# ARK.net
KiCad netlist of a schematic drawn in EAGLE
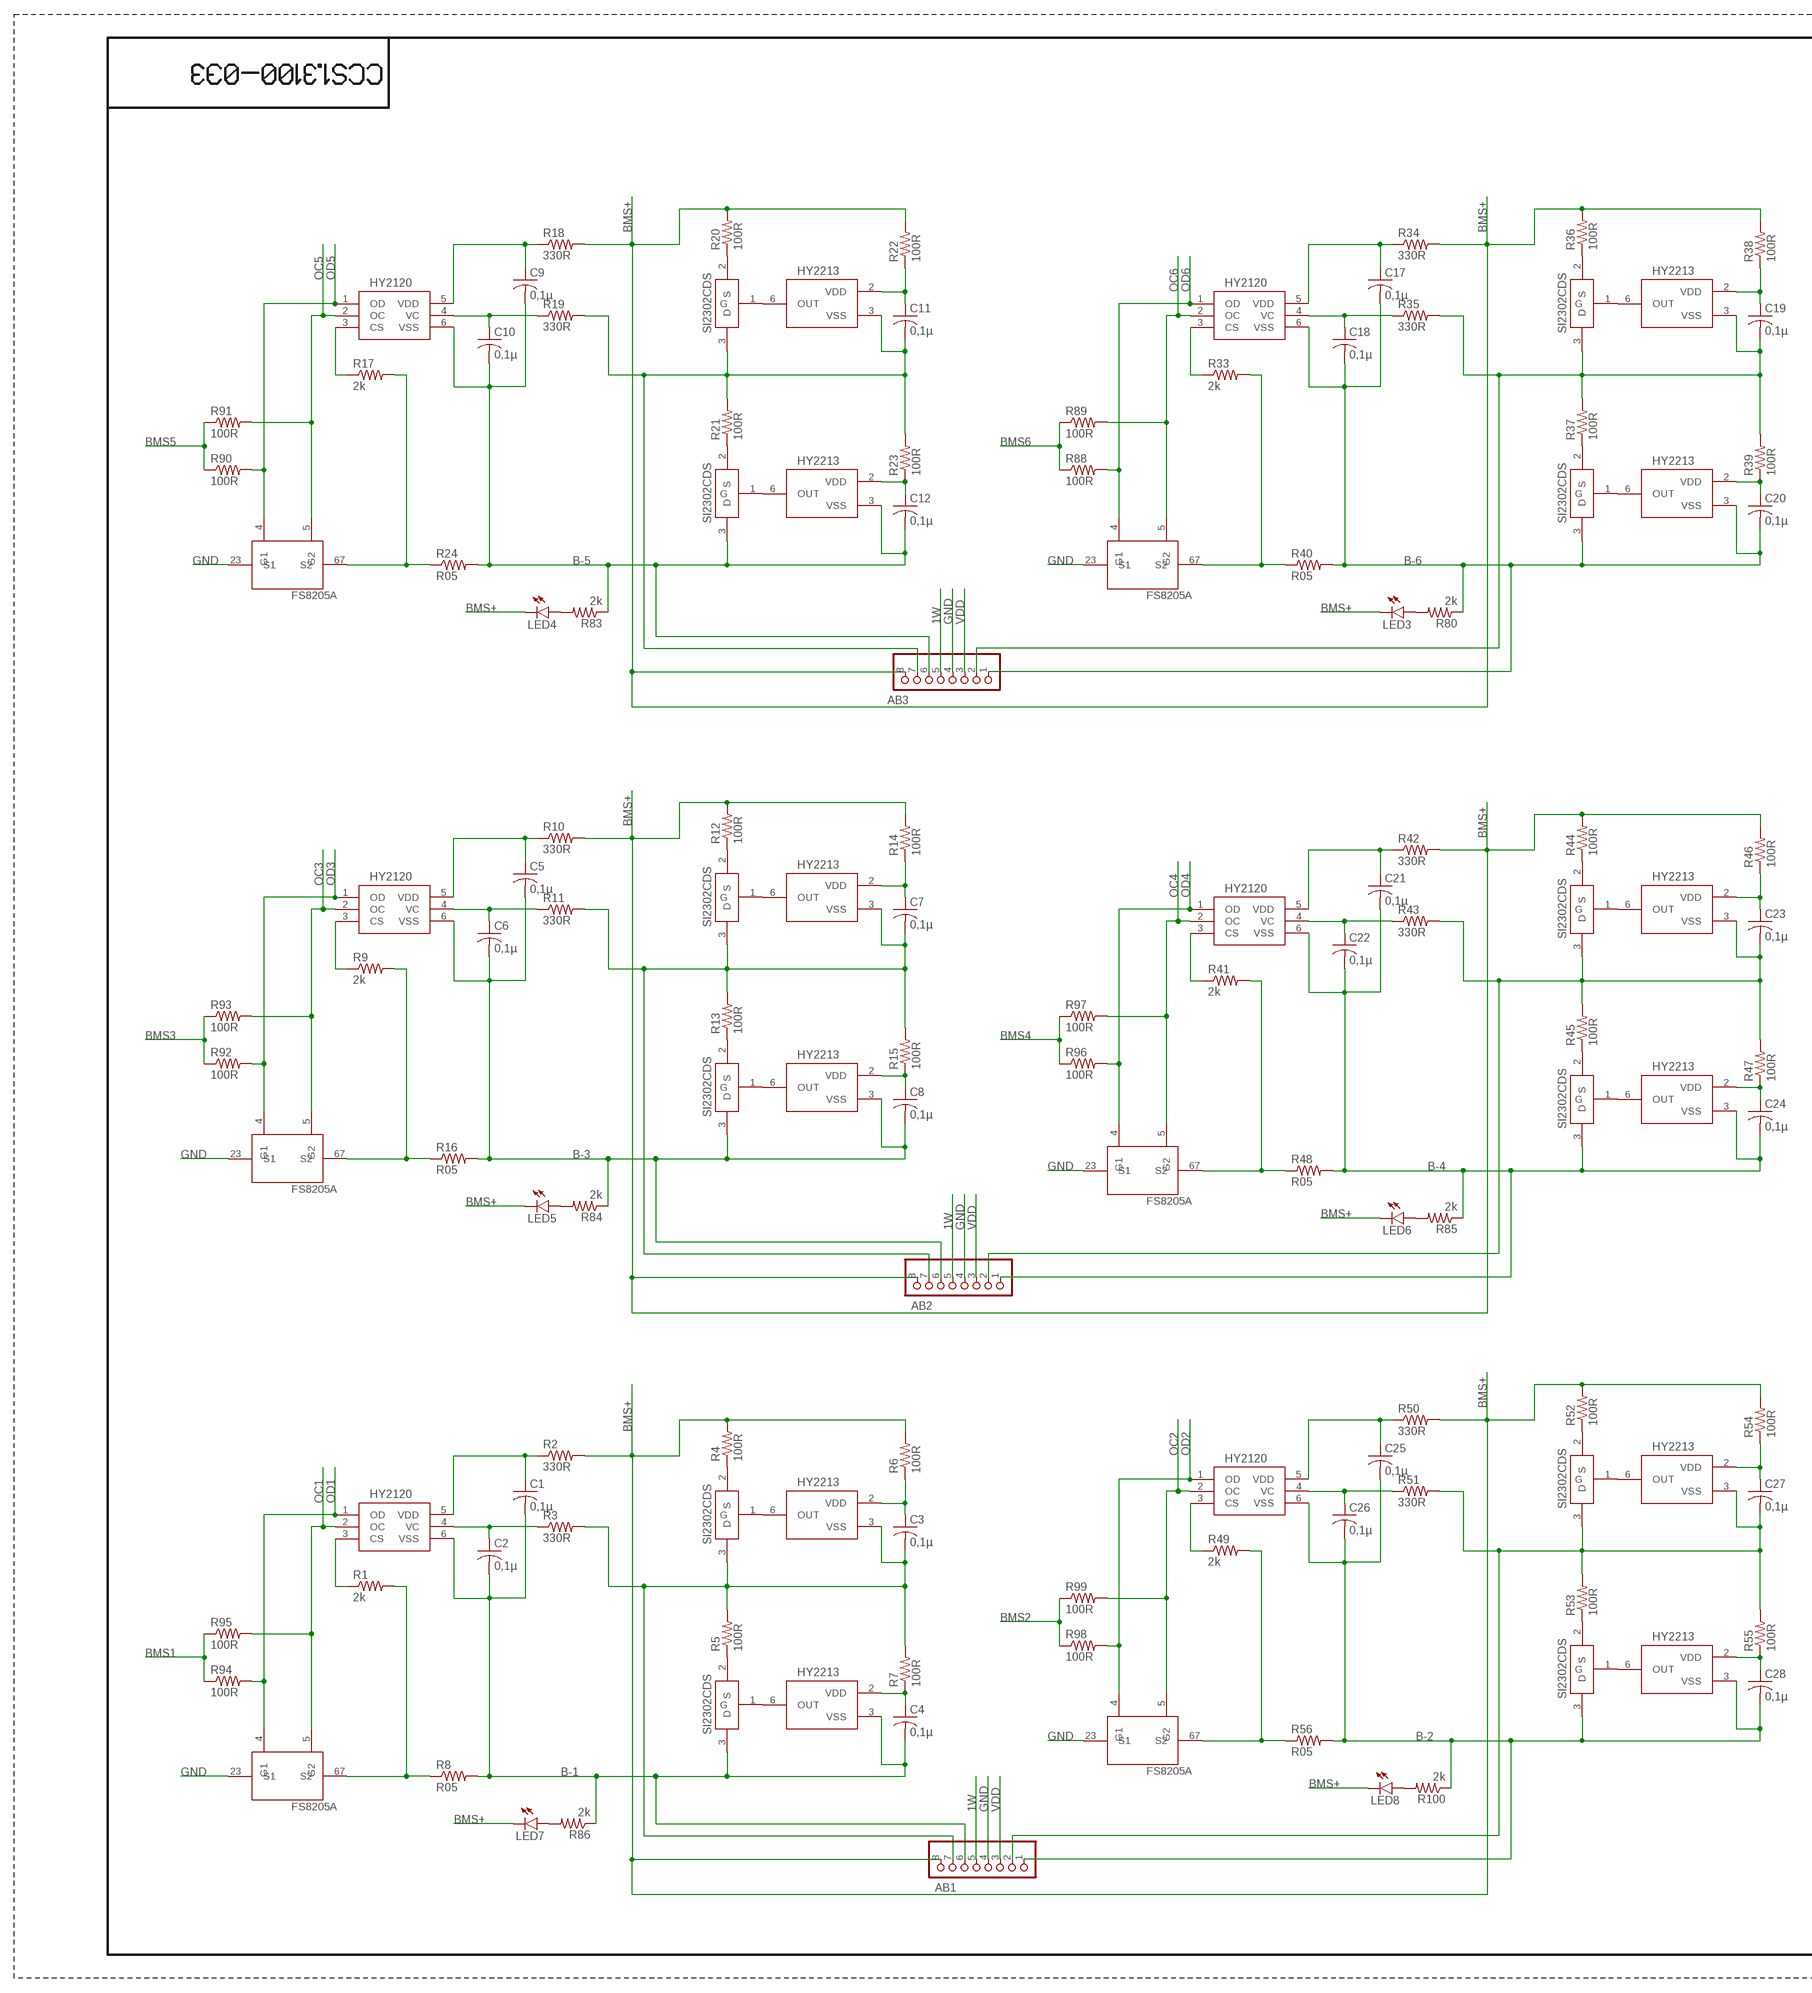
[diagram p0: schematic, sheet 1, part 1 of 2]
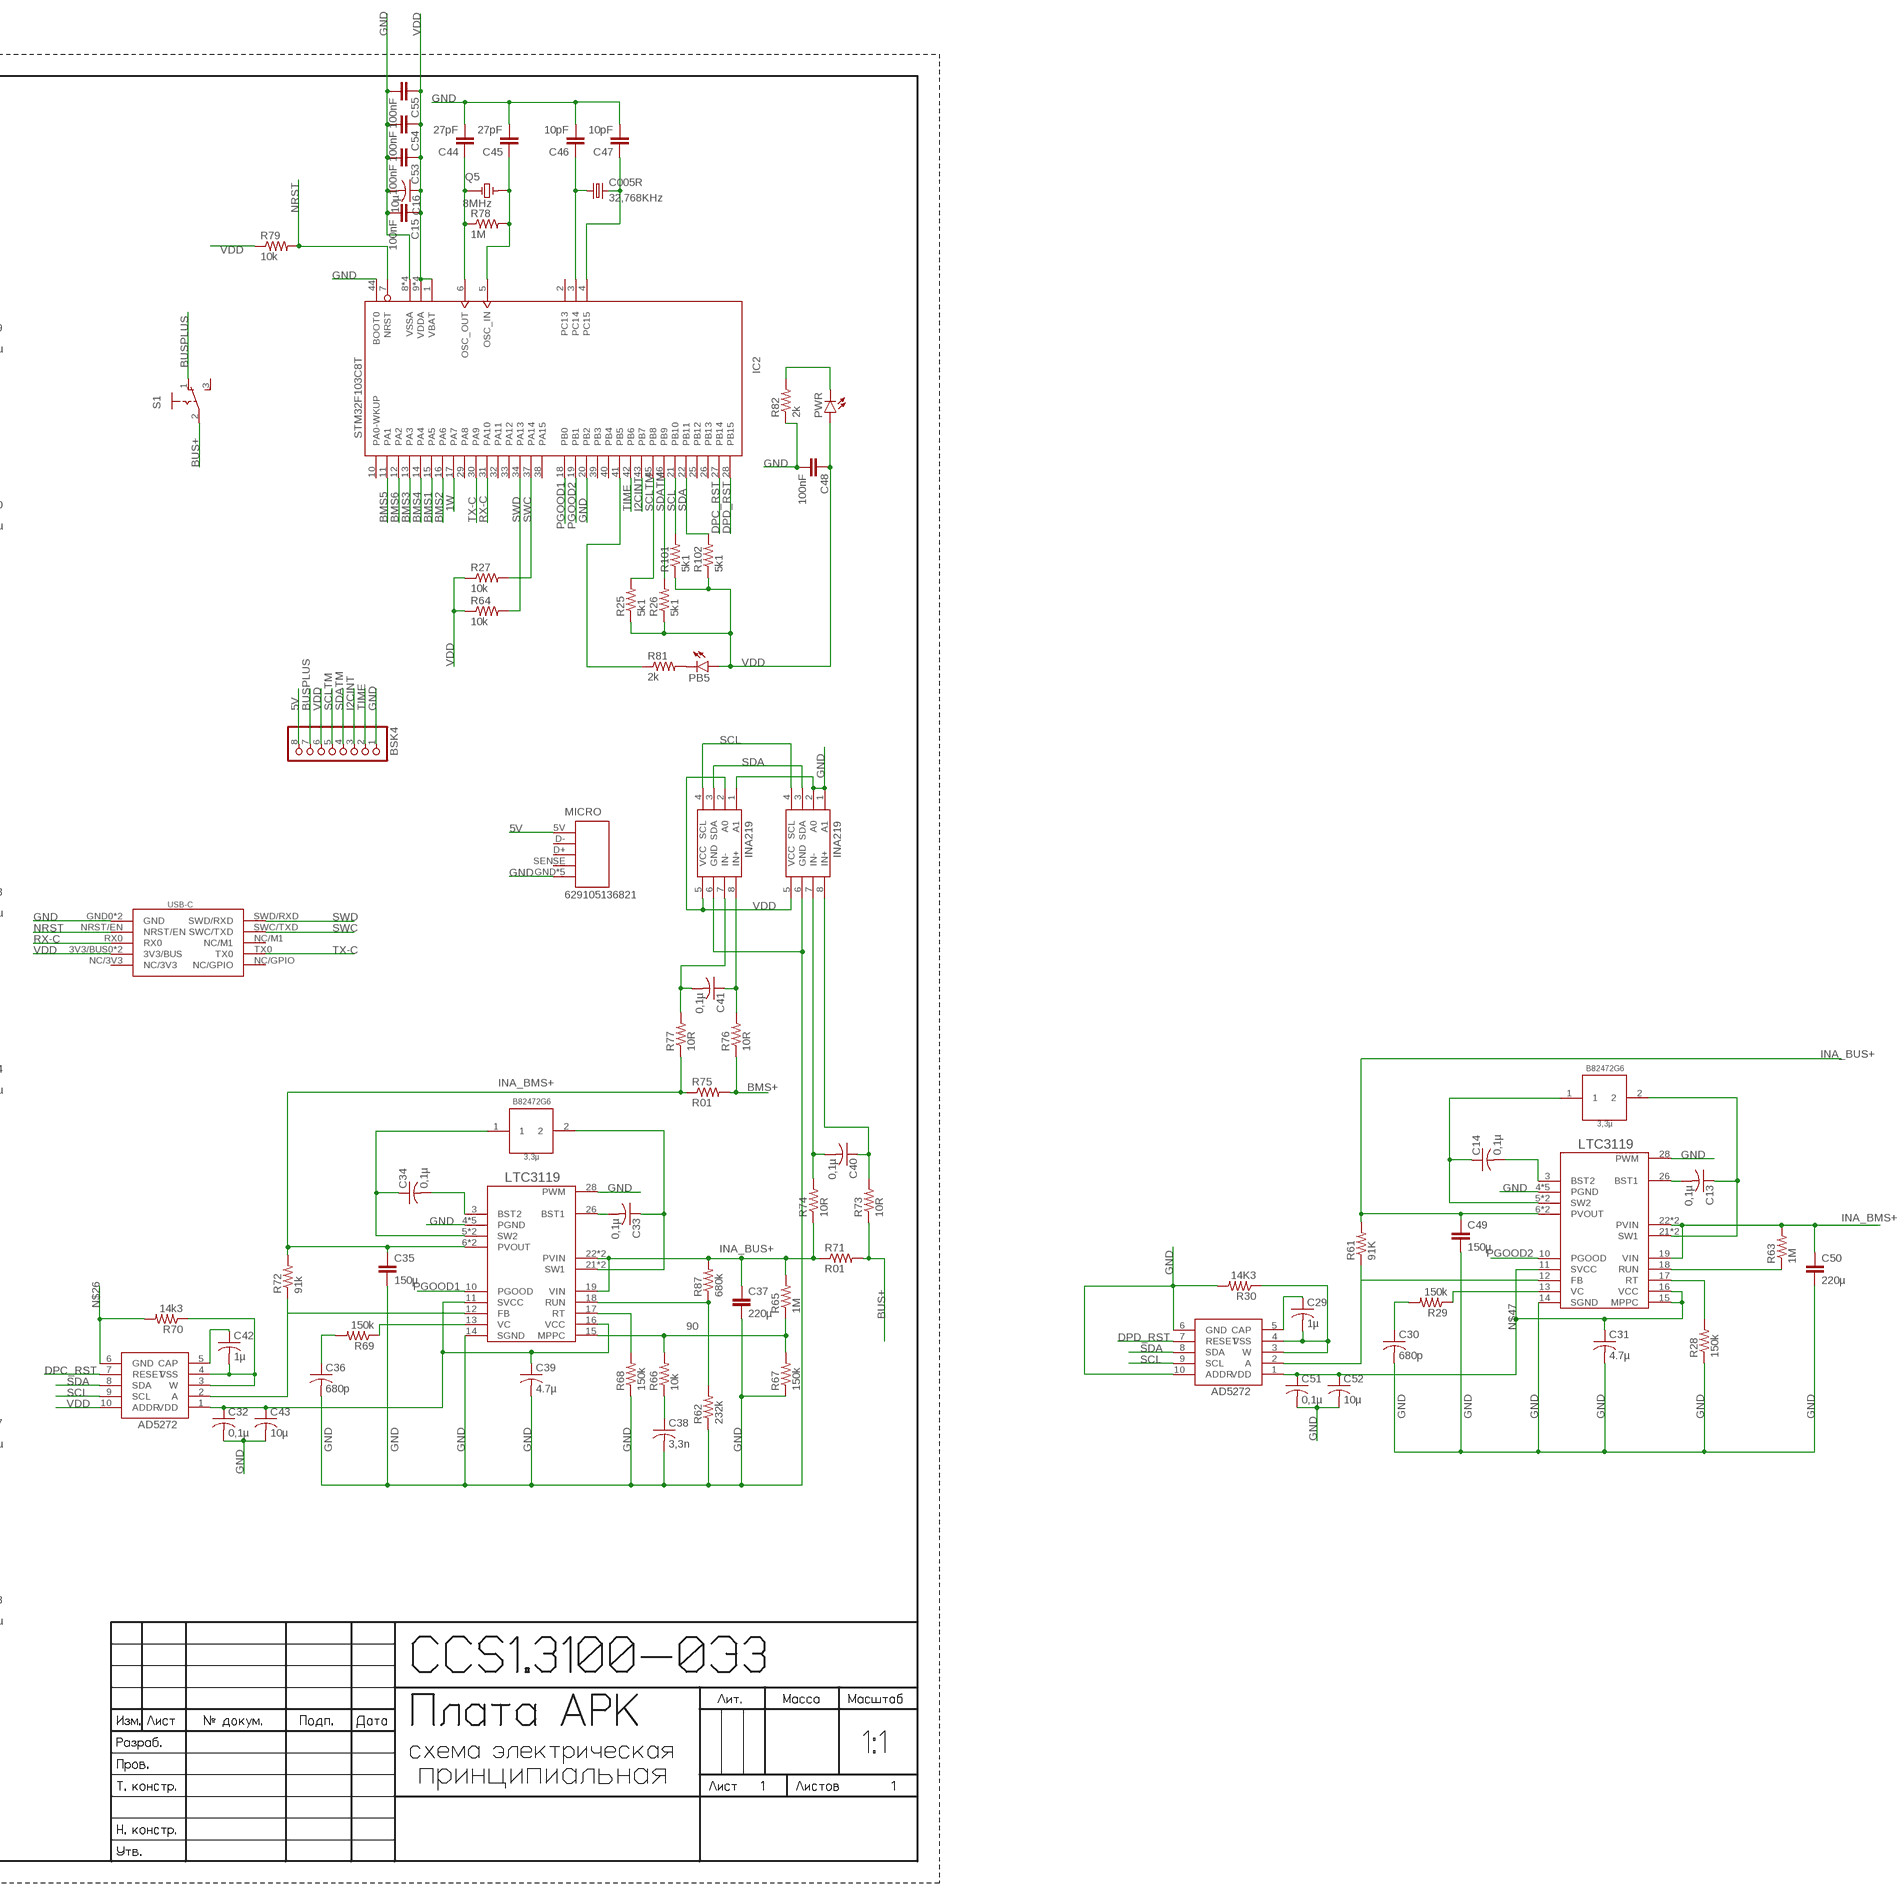
[diagram p1: schematic, sheet 1, part 2 of 2]

(export (version "E")
  (design (tool "Eeschema 10.0.6"))
  (components
    (comp (ref "3,3µH")
      (value "3,3µ")
      (footprint "eagle-import:B82472G6")
      (libsource (lib "eagle-import") (part "B82472G6"))
    )
    (comp (ref "3,3µH1")
      (value "3,3µ")
      (footprint "eagle-import:B82472G6")
      (libsource (lib "eagle-import") (part "B82472G6"))
    )
    (comp (ref "AB1")
      (value "PINHD-1X8")
      (footprint "eagle-import:1X08")
      (libsource (lib "eagle-import") (part "PINHD-1X8"))
    )
    (comp (ref "AB2")
      (value "PINHD-1X8")
      (footprint "eagle-import:1X08")
      (libsource (lib "eagle-import") (part "PINHD-1X8"))
    )
    (comp (ref "AB3")
      (value "PINHD-1X8")
      (footprint "eagle-import:1X08")
      (libsource (lib "eagle-import") (part "PINHD-1X8"))
    )
    (comp (ref "AD5272#2")
      (value "AD5272")
      (footprint "eagle-import:AD5272")
      (libsource (lib "eagle-import") (part "AD5272"))
    )
    (comp (ref "BSK4")
      (value "PINHD-1X8")
      (footprint "eagle-import:1X08")
      (libsource (lib "eagle-import") (part "PINHD-1X8"))
    )
    (comp (ref "C1")
      (value "0,1µ")
      (footprint "eagle-import:C0603")
      (libsource (lib "eagle-import") (part "C-USC0603"))
    )
    (comp (ref "C2")
      (value "0,1µ")
      (footprint "eagle-import:C0603")
      (libsource (lib "eagle-import") (part "C-USC0603"))
    )
    (comp (ref "C3")
      (value "0,1µ")
      (footprint "eagle-import:C0603")
      (libsource (lib "eagle-import") (part "C-USC0603"))
    )
    (comp (ref "C4")
      (value "0,1µ")
      (footprint "eagle-import:C0603")
      (libsource (lib "eagle-import") (part "C-USC0603"))
    )
    (comp (ref "C5")
      (value "0,1µ")
      (footprint "eagle-import:C0603")
      (libsource (lib "eagle-import") (part "C-USC0603"))
    )
    (comp (ref "C005R")
      (value "32,768KHz")
      (footprint "eagle-import:C005R")
      (libsource (lib "eagle-import") (part "C005R"))
    )
    (comp (ref "C6")
      (value "0,1µ")
      (footprint "eagle-import:C0603")
      (libsource (lib "eagle-import") (part "C-USC0603"))
    )
    (comp (ref "C7")
      (value "0,1µ")
      (footprint "eagle-import:C0603")
      (libsource (lib "eagle-import") (part "C-USC0603"))
    )
    (comp (ref "C8")
      (value "0,1µ")
      (footprint "eagle-import:C0603")
      (libsource (lib "eagle-import") (part "C-USC0603"))
    )
    (comp (ref "C9")
      (value "0,1µ")
      (footprint "eagle-import:C0603")
      (libsource (lib "eagle-import") (part "C-USC0603"))
    )
    (comp (ref "C10")
      (value "0,1µ")
      (footprint "eagle-import:C0603")
      (libsource (lib "eagle-import") (part "C-USC0603"))
    )
    (comp (ref "C11")
      (value "0,1µ")
      (footprint "eagle-import:C0603")
      (libsource (lib "eagle-import") (part "C-USC0603"))
    )
    (comp (ref "C12")
      (value "0,1µ")
      (footprint "eagle-import:C0603")
      (libsource (lib "eagle-import") (part "C-USC0603"))
    )
    (comp (ref "C13")
      (value "0,1µ")
      (footprint "eagle-import:C0603")
      (libsource (lib "eagle-import") (part "C-USC0603"))
    )
    (comp (ref "C14")
      (value "0,1µ")
      (footprint "eagle-import:C0603")
      (libsource (lib "eagle-import") (part "C-USC0603"))
    )
    (comp (ref "C15")
      (value "100nF")
      (footprint "eagle-import:C0603")
      (libsource (lib "eagle-import") (part "C-EUC0603"))
    )
    (comp (ref "C16")
      (value "10µ")
      (footprint "eagle-import:C1206")
      (libsource (lib "eagle-import") (part "C-USC1206"))
    )
    (comp (ref "C17")
      (value "0,1µ")
      (footprint "eagle-import:C0603")
      (libsource (lib "eagle-import") (part "C-USC0603"))
    )
    (comp (ref "C18")
      (value "0,1µ")
      (footprint "eagle-import:C0603")
      (libsource (lib "eagle-import") (part "C-USC0603"))
    )
    (comp (ref "C19")
      (value "0,1µ")
      (footprint "eagle-import:C0603")
      (libsource (lib "eagle-import") (part "C-USC0603"))
    )
    (comp (ref "C20")
      (value "0,1µ")
      (footprint "eagle-import:C0603")
      (libsource (lib "eagle-import") (part "C-USC0603"))
    )
    (comp (ref "C21")
      (value "0,1µ")
      (footprint "eagle-import:C0603")
      (libsource (lib "eagle-import") (part "C-USC0603"))
    )
    (comp (ref "C22")
      (value "0,1µ")
      (footprint "eagle-import:C0603")
      (libsource (lib "eagle-import") (part "C-USC0603"))
    )
    (comp (ref "C23")
      (value "0,1µ")
      (footprint "eagle-import:C0603")
      (libsource (lib "eagle-import") (part "C-USC0603"))
    )
    (comp (ref "C24")
      (value "0,1µ")
      (footprint "eagle-import:C0603")
      (libsource (lib "eagle-import") (part "C-USC0603"))
    )
    (comp (ref "C25")
      (value "0,1µ")
      (footprint "eagle-import:C0603")
      (libsource (lib "eagle-import") (part "C-USC0603"))
    )
    (comp (ref "C26")
      (value "0,1µ")
      (footprint "eagle-import:C0603")
      (libsource (lib "eagle-import") (part "C-USC0603"))
    )
    (comp (ref "C27")
      (value "0,1µ")
      (footprint "eagle-import:C0603")
      (libsource (lib "eagle-import") (part "C-USC0603"))
    )
    (comp (ref "C28")
      (value "0,1µ")
      (footprint "eagle-import:C0603")
      (libsource (lib "eagle-import") (part "C-USC0603"))
    )
    (comp (ref "C29")
      (value "1µ")
      (footprint "eagle-import:C0603")
      (libsource (lib "eagle-import") (part "C-USC0603"))
    )
    (comp (ref "C30")
      (value "680p")
      (footprint "eagle-import:C0603")
      (libsource (lib "eagle-import") (part "C-USC0603"))
    )
    (comp (ref "C31")
      (value "4.7µ")
      (footprint "eagle-import:C1206")
      (libsource (lib "eagle-import") (part "C-USC1206"))
    )
    (comp (ref "C32")
      (value "0,1µ")
      (footprint "eagle-import:C0603")
      (libsource (lib "eagle-import") (part "C-USC0603"))
    )
    (comp (ref "C33")
      (value "0,1µ")
      (footprint "eagle-import:C0603")
      (libsource (lib "eagle-import") (part "C-USC0603"))
    )
    (comp (ref "C34")
      (value "0,1µ")
      (footprint "eagle-import:C0603")
      (libsource (lib "eagle-import") (part "C-USC0603"))
    )
    (comp (ref "C35")
      (value "150µ")
      (footprint "eagle-import:ECAP150")
      (libsource (lib "eagle-import") (part "ECAPECAP150"))
    )
    (comp (ref "C36")
      (value "680p")
      (footprint "eagle-import:C0603")
      (libsource (lib "eagle-import") (part "C-USC0603"))
    )
    (comp (ref "C37")
      (value "220µ")
      (footprint "eagle-import:ECAP220")
      (libsource (lib "eagle-import") (part "ECAPECAP220"))
    )
    (comp (ref "C38")
      (value "3,3n")
      (footprint "eagle-import:C0603")
      (libsource (lib "eagle-import") (part "C-USC0603"))
    )
    (comp (ref "C39")
      (value "4.7µ")
      (footprint "eagle-import:C1206")
      (libsource (lib "eagle-import") (part "C-USC1206"))
    )
    (comp (ref "C40")
      (value "0,1µ")
      (footprint "eagle-import:C0603")
      (libsource (lib "eagle-import") (part "C-USC0603"))
    )
    (comp (ref "C41")
      (value "0,1µ")
      (footprint "eagle-import:C0603")
      (libsource (lib "eagle-import") (part "C-USC0603"))
    )
    (comp (ref "C42")
      (value "1µ")
      (footprint "eagle-import:C0603")
      (libsource (lib "eagle-import") (part "C-USC0603"))
    )
    (comp (ref "C43")
      (value "10µ")
      (footprint "eagle-import:C1206")
      (libsource (lib "eagle-import") (part "C-USC1206"))
    )
    (comp (ref "C44")
      (value "27pF")
      (footprint "eagle-import:C0603")
      (libsource (lib "eagle-import") (part "C-EUC0603"))
    )
    (comp (ref "C45")
      (value "27pF")
      (footprint "eagle-import:C0603")
      (libsource (lib "eagle-import") (part "C-EUC0603"))
    )
    (comp (ref "C46")
      (value "10pF")
      (footprint "eagle-import:C0603")
      (libsource (lib "eagle-import") (part "C-EUC0603"))
    )
    (comp (ref "C47")
      (value "10pF")
      (footprint "eagle-import:C0603")
      (libsource (lib "eagle-import") (part "C-EUC0603"))
    )
    (comp (ref "C48")
      (value "100nF")
      (footprint "eagle-import:C0603")
      (libsource (lib "eagle-import") (part "C-EUC0603"))
    )
    (comp (ref "C49")
      (value "150µ")
      (footprint "eagle-import:ECAP150")
      (libsource (lib "eagle-import") (part "ECAPECAP150"))
    )
    (comp (ref "C50")
      (value "220µ")
      (footprint "eagle-import:ECAP220")
      (libsource (lib "eagle-import") (part "ECAPECAP220"))
    )
    (comp (ref "C51")
      (value "0,1µ")
      (footprint "eagle-import:C0603")
      (libsource (lib "eagle-import") (part "C-USC0603"))
    )
    (comp (ref "C52")
      (value "10µ")
      (footprint "eagle-import:C1206")
      (libsource (lib "eagle-import") (part "C-USC1206"))
    )
    (comp (ref "C53")
      (value "100nF")
      (footprint "eagle-import:C0603")
      (libsource (lib "eagle-import") (part "C-EUC0603"))
    )
    (comp (ref "C54")
      (value "100nF")
      (footprint "eagle-import:C0603")
      (libsource (lib "eagle-import") (part "C-EUC0603"))
    )
    (comp (ref "C55")
      (value "100nF")
      (footprint "eagle-import:C0603")
      (libsource (lib "eagle-import") (part "C-EUC0603"))
    )
    (comp (ref "IC2")
      (value "STM32F103C8T")
      (footprint "eagle-import:LQFP48")
      (libsource (lib "eagle-import") (part "STM32F103CT8"))
    )
    (comp (ref "INA219#1")
      (value "INA219AID")
      (footprint "eagle-import:INA219AID")
      (libsource (lib "eagle-import") (part "INA219AID"))
    )
    (comp (ref "LED3")
      (value "LEDCHIPLED_0603")
      (footprint "eagle-import:CHIPLED_0603")
      (libsource (lib "eagle-import") (part "LEDCHIPLED_0603"))
    )
    (comp (ref "LED4")
      (value "LEDCHIPLED_0603")
      (footprint "eagle-import:CHIPLED_0603")
      (libsource (lib "eagle-import") (part "LEDCHIPLED_0603"))
    )
    (comp (ref "LED5")
      (value "LEDCHIPLED_0603")
      (footprint "eagle-import:CHIPLED_0603")
      (libsource (lib "eagle-import") (part "LEDCHIPLED_0603"))
    )
    (comp (ref "LED6")
      (value "LEDCHIPLED_0603")
      (footprint "eagle-import:CHIPLED_0603")
      (libsource (lib "eagle-import") (part "LEDCHIPLED_0603"))
    )
    (comp (ref "LED7")
      (value "LEDCHIPLED_0603")
      (footprint "eagle-import:CHIPLED_0603")
      (libsource (lib "eagle-import") (part "LEDCHIPLED_0603"))
    )
    (comp (ref "LED8")
      (value "LEDCHIPLED_0603")
      (footprint "eagle-import:CHIPLED_0603")
      (libsource (lib "eagle-import") (part "LEDCHIPLED_0603"))
    )
    (comp (ref "MICRO")
      (value "629105136821")
      (footprint "eagle-import:629105136821")
      (libsource (lib "eagle-import") (part "629105136821"))
    )
    (comp (ref "PB5")
      (value "LEDCHIPLED_0603")
      (footprint "eagle-import:CHIPLED_0603")
      (libsource (lib "eagle-import") (part "LEDCHIPLED_0603"))
    )
    (comp (ref "PWR")
      (value "LEDCHIPLED_0603")
      (footprint "eagle-import:CHIPLED_0603")
      (libsource (lib "eagle-import") (part "LEDCHIPLED_0603"))
    )
    (comp (ref "Q5")
      (value "8MHz")
      (footprint "eagle-import:XTAL_9C-8.000MEEJ-T")
      (fields (field (name "MF") "TXC CORPORATION") (field (name "MP") "9C-8.000MEEJ-T"))
      (libsource (lib "eagle-import") (part "9C-8.000MEEJ-T"))
    )
    (comp (ref "R1")
      (value "2k")
      (footprint "eagle-import:R0603")
      (libsource (lib "eagle-import") (part "resistor_348_R-US_R0603"))
    )
    (comp (ref "R2")
      (value "330R")
      (footprint "eagle-import:R0603")
      (libsource (lib "eagle-import") (part "resistor_348_R-US_R0603"))
    )
    (comp (ref "R3")
      (value "330R")
      (footprint "eagle-import:R0603")
      (libsource (lib "eagle-import") (part "resistor_348_R-US_R0603"))
    )
    (comp (ref "R4")
      (value "100R")
      (footprint "eagle-import:R0603")
      (libsource (lib "eagle-import") (part "resistor_348_R-US_R0603"))
    )
    (comp (ref "R5")
      (value "100R")
      (footprint "eagle-import:R0603")
      (libsource (lib "eagle-import") (part "resistor_348_R-US_R0603"))
    )
    (comp (ref "R6")
      (value "100R")
      (footprint "eagle-import:R0603")
      (libsource (lib "eagle-import") (part "resistor_348_R-US_R0603"))
    )
    (comp (ref "R7")
      (value "100R")
      (footprint "eagle-import:R0603")
      (libsource (lib "eagle-import") (part "resistor_348_R-US_R0603"))
    )
    (comp (ref "R8")
      (value "R05")
      (footprint "eagle-import:R2512")
      (libsource (lib "eagle-import") (part "R-US_R2512"))
    )
    (comp (ref "R9")
      (value "2k")
      (footprint "eagle-import:R0603")
      (libsource (lib "eagle-import") (part "resistor_348_R-US_R0603"))
    )
    (comp (ref "R10")
      (value "330R")
      (footprint "eagle-import:R0603")
      (libsource (lib "eagle-import") (part "resistor_348_R-US_R0603"))
    )
    (comp (ref "R11")
      (value "330R")
      (footprint "eagle-import:R0603")
      (libsource (lib "eagle-import") (part "resistor_348_R-US_R0603"))
    )
    (comp (ref "R12")
      (value "100R")
      (footprint "eagle-import:R0603")
      (libsource (lib "eagle-import") (part "resistor_348_R-US_R0603"))
    )
    (comp (ref "R13")
      (value "100R")
      (footprint "eagle-import:R0603")
      (libsource (lib "eagle-import") (part "resistor_348_R-US_R0603"))
    )
    (comp (ref "R14")
      (value "100R")
      (footprint "eagle-import:R0603")
      (libsource (lib "eagle-import") (part "resistor_348_R-US_R0603"))
    )
    (comp (ref "R15")
      (value "100R")
      (footprint "eagle-import:R0603")
      (libsource (lib "eagle-import") (part "resistor_348_R-US_R0603"))
    )
    (comp (ref "R16")
      (value "R05")
      (footprint "eagle-import:R2512")
      (libsource (lib "eagle-import") (part "R-US_R2512"))
    )
    (comp (ref "R17")
      (value "2k")
      (footprint "eagle-import:R0603")
      (libsource (lib "eagle-import") (part "resistor_348_R-US_R0603"))
    )
    (comp (ref "R18")
      (value "330R")
      (footprint "eagle-import:R0603")
      (libsource (lib "eagle-import") (part "resistor_348_R-US_R0603"))
    )
    (comp (ref "R19")
      (value "330R")
      (footprint "eagle-import:R0603")
      (libsource (lib "eagle-import") (part "resistor_348_R-US_R0603"))
    )
    (comp (ref "R20")
      (value "100R")
      (footprint "eagle-import:R0603")
      (libsource (lib "eagle-import") (part "resistor_348_R-US_R0603"))
    )
    (comp (ref "R21")
      (value "100R")
      (footprint "eagle-import:R0603")
      (libsource (lib "eagle-import") (part "resistor_348_R-US_R0603"))
    )
    (comp (ref "R22")
      (value "100R")
      (footprint "eagle-import:R0603")
      (libsource (lib "eagle-import") (part "resistor_348_R-US_R0603"))
    )
    (comp (ref "R23")
      (value "100R")
      (footprint "eagle-import:R0603")
      (libsource (lib "eagle-import") (part "resistor_348_R-US_R0603"))
    )
    (comp (ref "R24")
      (value "R05")
      (footprint "eagle-import:R2512")
      (libsource (lib "eagle-import") (part "R-US_R2512"))
    )
    (comp (ref "R25")
      (value "5k1")
      (footprint "eagle-import:R0603")
      (libsource (lib "eagle-import") (part "resistor_348_R-US_R0603"))
    )
    (comp (ref "R26")
      (value "5k1")
      (footprint "eagle-import:R0603")
      (libsource (lib "eagle-import") (part "resistor_348_R-US_R0603"))
    )
    (comp (ref "R27")
      (value "10k")
      (footprint "eagle-import:R0603")
      (libsource (lib "eagle-import") (part "resistor_348_R-US_R0603"))
    )
    (comp (ref "R28")
      (value "150k")
      (footprint "eagle-import:R0603")
      (libsource (lib "eagle-import") (part "resistor_348_R-US_R0603"))
    )
    (comp (ref "R29")
      (value "150k")
      (footprint "eagle-import:R0603")
      (libsource (lib "eagle-import") (part "resistor_348_R-US_R0603"))
    )
    (comp (ref "R30")
      (value "14K3")
      (footprint "eagle-import:R0603")
      (libsource (lib "eagle-import") (part "resistor_348_R-US_R0603"))
    )
    (comp (ref "R33")
      (value "2k")
      (footprint "eagle-import:R0603")
      (libsource (lib "eagle-import") (part "resistor_348_R-US_R0603"))
    )
    (comp (ref "R34")
      (value "330R")
      (footprint "eagle-import:R0603")
      (libsource (lib "eagle-import") (part "resistor_348_R-US_R0603"))
    )
    (comp (ref "R35")
      (value "330R")
      (footprint "eagle-import:R0603")
      (libsource (lib "eagle-import") (part "resistor_348_R-US_R0603"))
    )
    (comp (ref "R36")
      (value "100R")
      (footprint "eagle-import:R0603")
      (libsource (lib "eagle-import") (part "resistor_348_R-US_R0603"))
    )
    (comp (ref "R37")
      (value "100R")
      (footprint "eagle-import:R0603")
      (libsource (lib "eagle-import") (part "resistor_348_R-US_R0603"))
    )
    (comp (ref "R38")
      (value "100R")
      (footprint "eagle-import:R0603")
      (libsource (lib "eagle-import") (part "resistor_348_R-US_R0603"))
    )
    (comp (ref "R39")
      (value "100R")
      (footprint "eagle-import:R0603")
      (libsource (lib "eagle-import") (part "resistor_348_R-US_R0603"))
    )
    (comp (ref "R40")
      (value "R05")
      (footprint "eagle-import:R2512")
      (libsource (lib "eagle-import") (part "R-US_R2512"))
    )
    (comp (ref "R41")
      (value "2k")
      (footprint "eagle-import:R0603")
      (libsource (lib "eagle-import") (part "resistor_348_R-US_R0603"))
    )
    (comp (ref "R42")
      (value "330R")
      (footprint "eagle-import:R0603")
      (libsource (lib "eagle-import") (part "resistor_348_R-US_R0603"))
    )
    (comp (ref "R43")
      (value "330R")
      (footprint "eagle-import:R0603")
      (libsource (lib "eagle-import") (part "resistor_348_R-US_R0603"))
    )
    (comp (ref "R44")
      (value "100R")
      (footprint "eagle-import:R0603")
      (libsource (lib "eagle-import") (part "resistor_348_R-US_R0603"))
    )
    (comp (ref "R45")
      (value "100R")
      (footprint "eagle-import:R0603")
      (libsource (lib "eagle-import") (part "resistor_348_R-US_R0603"))
    )
    (comp (ref "R46")
      (value "100R")
      (footprint "eagle-import:R0603")
      (libsource (lib "eagle-import") (part "resistor_348_R-US_R0603"))
    )
    (comp (ref "R47")
      (value "100R")
      (footprint "eagle-import:R0603")
      (libsource (lib "eagle-import") (part "resistor_348_R-US_R0603"))
    )
    (comp (ref "R48")
      (value "R05")
      (footprint "eagle-import:R2512")
      (libsource (lib "eagle-import") (part "R-US_R2512"))
    )
    (comp (ref "R49")
      (value "2k")
      (footprint "eagle-import:R0603")
      (libsource (lib "eagle-import") (part "resistor_348_R-US_R0603"))
    )
    (comp (ref "R50")
      (value "330R")
      (footprint "eagle-import:R0603")
      (libsource (lib "eagle-import") (part "resistor_348_R-US_R0603"))
    )
    (comp (ref "R51")
      (value "330R")
      (footprint "eagle-import:R0603")
      (libsource (lib "eagle-import") (part "resistor_348_R-US_R0603"))
    )
    (comp (ref "R52")
      (value "100R")
      (footprint "eagle-import:R0603")
      (libsource (lib "eagle-import") (part "resistor_348_R-US_R0603"))
    )
    (comp (ref "R53")
      (value "100R")
      (footprint "eagle-import:R0603")
      (libsource (lib "eagle-import") (part "resistor_348_R-US_R0603"))
    )
    (comp (ref "R54")
      (value "100R")
      (footprint "eagle-import:R0603")
      (libsource (lib "eagle-import") (part "resistor_348_R-US_R0603"))
    )
    (comp (ref "R55")
      (value "100R")
      (footprint "eagle-import:R0603")
      (libsource (lib "eagle-import") (part "resistor_348_R-US_R0603"))
    )
    (comp (ref "R56")
      (value "R05")
      (footprint "eagle-import:R2512")
      (libsource (lib "eagle-import") (part "R-US_R2512"))
    )
    (comp (ref "R61")
      (value "91K")
      (footprint "eagle-import:R0603")
      (libsource (lib "eagle-import") (part "resistor_348_R-US_R0603"))
    )
    (comp (ref "R62")
      (value "232k")
      (footprint "eagle-import:R0603")
      (libsource (lib "eagle-import") (part "resistor_348_R-US_R0603"))
    )
    (comp (ref "R63")
      (value "1M")
      (footprint "eagle-import:R0603")
      (libsource (lib "eagle-import") (part "resistor_348_R-US_R0603"))
    )
    (comp (ref "R64")
      (value "10k")
      (footprint "eagle-import:R0603")
      (libsource (lib "eagle-import") (part "resistor_348_R-US_R0603"))
    )
    (comp (ref "R65")
      (value "1M")
      (footprint "eagle-import:R0603")
      (libsource (lib "eagle-import") (part "resistor_348_R-US_R0603"))
    )
    (comp (ref "R66")
      (value "10k")
      (footprint "eagle-import:R0603")
      (libsource (lib "eagle-import") (part "resistor_348_R-US_R0603"))
    )
    (comp (ref "R67")
      (value "150k")
      (footprint "eagle-import:R0603")
      (libsource (lib "eagle-import") (part "resistor_348_R-US_R0603"))
    )
    (comp (ref "R68")
      (value "150k")
      (footprint "eagle-import:R0603")
      (libsource (lib "eagle-import") (part "resistor_348_R-US_R0603"))
    )
    (comp (ref "R69")
      (value "150k")
      (footprint "eagle-import:R0603")
      (libsource (lib "eagle-import") (part "resistor_348_R-US_R0603"))
    )
    (comp (ref "R70")
      (value "14k3")
      (footprint "eagle-import:R0603")
      (libsource (lib "eagle-import") (part "resistor_348_R-US_R0603"))
    )
    (comp (ref "R71")
      (value "R01")
      (footprint "eagle-import:R2512")
      (libsource (lib "eagle-import") (part "R-US_R2512"))
    )
    (comp (ref "R72")
      (value "91k")
      (footprint "eagle-import:R0603")
      (libsource (lib "eagle-import") (part "resistor_348_R-US_R0603"))
    )
    (comp (ref "R73")
      (value "10R")
      (footprint "eagle-import:R0603")
      (libsource (lib "eagle-import") (part "resistor_348_R-US_R0603"))
    )
    (comp (ref "R74")
      (value "10R")
      (footprint "eagle-import:R0603")
      (libsource (lib "eagle-import") (part "resistor_348_R-US_R0603"))
    )
    (comp (ref "R75")
      (value "R01")
      (footprint "eagle-import:R2512")
      (libsource (lib "eagle-import") (part "R-US_R2512"))
    )
    (comp (ref "R76")
      (value "10R")
      (footprint "eagle-import:R0603")
      (libsource (lib "eagle-import") (part "resistor_348_R-US_R0603"))
    )
    (comp (ref "R77")
      (value "10R")
      (footprint "eagle-import:R0603")
      (libsource (lib "eagle-import") (part "resistor_348_R-US_R0603"))
    )
    (comp (ref "R78")
      (value "1M")
      (footprint "eagle-import:R0603")
      (libsource (lib "eagle-import") (part "resistor_348_R-US_R0603"))
    )
    (comp (ref "R79")
      (value "10k")
      (footprint "eagle-import:R0603")
      (libsource (lib "eagle-import") (part "resistor_348_R-US_R0603"))
    )
    (comp (ref "R80")
      (value "2k")
      (footprint "eagle-import:R0603")
      (libsource (lib "eagle-import") (part "resistor_348_R-US_R0603"))
    )
    (comp (ref "R81")
      (value "2k")
      (footprint "eagle-import:R0603")
      (libsource (lib "eagle-import") (part "resistor_348_R-US_R0603"))
    )
    (comp (ref "R82")
      (value "2k")
      (footprint "eagle-import:R0603")
      (libsource (lib "eagle-import") (part "resistor_348_R-US_R0603"))
    )
    (comp (ref "R83")
      (value "2k")
      (footprint "eagle-import:R0603")
      (libsource (lib "eagle-import") (part "resistor_348_R-US_R0603"))
    )
    (comp (ref "R84")
      (value "2k")
      (footprint "eagle-import:R0603")
      (libsource (lib "eagle-import") (part "resistor_348_R-US_R0603"))
    )
    (comp (ref "R85")
      (value "2k")
      (footprint "eagle-import:R0603")
      (libsource (lib "eagle-import") (part "resistor_348_R-US_R0603"))
    )
    (comp (ref "R86")
      (value "2k")
      (footprint "eagle-import:R0603")
      (libsource (lib "eagle-import") (part "resistor_348_R-US_R0603"))
    )
    (comp (ref "R87")
      (value "680k")
      (footprint "eagle-import:R0603")
      (libsource (lib "eagle-import") (part "resistor_348_R-US_R0603"))
    )
    (comp (ref "R88")
      (value "100R")
      (footprint "eagle-import:R0603")
      (libsource (lib "eagle-import") (part "resistor_348_R-US_R0603"))
    )
    (comp (ref "R89")
      (value "100R")
      (footprint "eagle-import:R0603")
      (libsource (lib "eagle-import") (part "resistor_348_R-US_R0603"))
    )
    (comp (ref "R90")
      (value "100R")
      (footprint "eagle-import:R0603")
      (libsource (lib "eagle-import") (part "resistor_348_R-US_R0603"))
    )
    (comp (ref "R91")
      (value "100R")
      (footprint "eagle-import:R0603")
      (libsource (lib "eagle-import") (part "resistor_348_R-US_R0603"))
    )
    (comp (ref "R92")
      (value "100R")
      (footprint "eagle-import:R0603")
      (libsource (lib "eagle-import") (part "resistor_348_R-US_R0603"))
    )
    (comp (ref "R93")
      (value "100R")
      (footprint "eagle-import:R0603")
      (libsource (lib "eagle-import") (part "resistor_348_R-US_R0603"))
    )
    (comp (ref "R94")
      (value "100R")
      (footprint "eagle-import:R0603")
      (libsource (lib "eagle-import") (part "resistor_348_R-US_R0603"))
    )
    (comp (ref "R95")
      (value "100R")
      (footprint "eagle-import:R0603")
      (libsource (lib "eagle-import") (part "resistor_348_R-US_R0603"))
    )
    (comp (ref "R96")
      (value "100R")
      (footprint "eagle-import:R0603")
      (libsource (lib "eagle-import") (part "resistor_348_R-US_R0603"))
    )
    (comp (ref "R97")
      (value "100R")
      (footprint "eagle-import:R0603")
      (libsource (lib "eagle-import") (part "resistor_348_R-US_R0603"))
    )
    (comp (ref "R98")
      (value "100R")
      (footprint "eagle-import:R0603")
      (libsource (lib "eagle-import") (part "resistor_348_R-US_R0603"))
    )
    (comp (ref "R99")
      (value "100R")
      (footprint "eagle-import:R0603")
      (libsource (lib "eagle-import") (part "resistor_348_R-US_R0603"))
    )
    (comp (ref "R100")
      (value "2k")
      (footprint "eagle-import:R0603")
      (libsource (lib "eagle-import") (part "resistor_348_R-US_R0603"))
    )
    (comp (ref "R101")
      (value "5k1")
      (footprint "eagle-import:R0603")
      (libsource (lib "eagle-import") (part "resistor_348_R-US_R0603"))
    )
    (comp (ref "R102")
      (value "5k1")
      (footprint "eagle-import:R0603")
      (libsource (lib "eagle-import") (part "resistor_348_R-US_R0603"))
    )
    (comp (ref "S1")
      (value "UNICS-SWITCH")
      (footprint "eagle-import:UNICS-SWITCH")
      (libsource (lib "eagle-import") (part "UNICS-SWITCH"))
    )
    (comp (ref "U$1")
      (value "FS8205A-")
      (footprint "eagle-import:FS8205A-")
      (libsource (lib "eagle-import") (part "FS8205A-"))
    )
    (comp (ref "U$3")
      (value "HY2120")
      (footprint "eagle-import:HY2120")
      (libsource (lib "eagle-import") (part "HY2120"))
    )
    (comp (ref "U$4")
      (value "HY2213")
      (footprint "eagle-import:HY2213")
      (libsource (lib "eagle-import") (part "HY2213"))
    )
    (comp (ref "U$5")
      (value "HY2213")
      (footprint "eagle-import:HY2213")
      (libsource (lib "eagle-import") (part "HY2213"))
    )
    (comp (ref "U$6")
      (value "SI2302CDS")
      (footprint "eagle-import:SI2302CDS")
      (libsource (lib "eagle-import") (part "SI2302CDS"))
    )
    (comp (ref "U$7")
      (value "SI2302CDS")
      (footprint "eagle-import:SI2302CDS")
      (libsource (lib "eagle-import") (part "SI2302CDS"))
    )
    (comp (ref "U$8")
      (value "FS8205A-")
      (footprint "eagle-import:FS8205A-")
      (libsource (lib "eagle-import") (part "FS8205A-"))
    )
    (comp (ref "U$10")
      (value "HY2120")
      (footprint "eagle-import:HY2120")
      (libsource (lib "eagle-import") (part "HY2120"))
    )
    (comp (ref "U$11")
      (value "HY2213")
      (footprint "eagle-import:HY2213")
      (libsource (lib "eagle-import") (part "HY2213"))
    )
    (comp (ref "U$12")
      (value "HY2213")
      (footprint "eagle-import:HY2213")
      (libsource (lib "eagle-import") (part "HY2213"))
    )
    (comp (ref "U$13")
      (value "SI2302CDS")
      (footprint "eagle-import:SI2302CDS")
      (libsource (lib "eagle-import") (part "SI2302CDS"))
    )
    (comp (ref "U$14")
      (value "SI2302CDS")
      (footprint "eagle-import:SI2302CDS")
      (libsource (lib "eagle-import") (part "SI2302CDS"))
    )
    (comp (ref "U$15")
      (value "FS8205A-")
      (footprint "eagle-import:FS8205A-")
      (libsource (lib "eagle-import") (part "FS8205A-"))
    )
    (comp (ref "U$16")
      (value "LTC3119")
      (footprint "eagle-import:LTC3119")
      (libsource (lib "eagle-import") (part "LTC3119"))
    )
    (comp (ref "U$17")
      (value "HY2120")
      (footprint "eagle-import:HY2120")
      (libsource (lib "eagle-import") (part "HY2120"))
    )
    (comp (ref "U$18")
      (value "HY2213")
      (footprint "eagle-import:HY2213")
      (libsource (lib "eagle-import") (part "HY2213"))
    )
    (comp (ref "U$19")
      (value "HY2213")
      (footprint "eagle-import:HY2213")
      (libsource (lib "eagle-import") (part "HY2213"))
    )
    (comp (ref "U$20")
      (value "SI2302CDS")
      (footprint "eagle-import:SI2302CDS")
      (libsource (lib "eagle-import") (part "SI2302CDS"))
    )
    (comp (ref "U$21")
      (value "SI2302CDS")
      (footprint "eagle-import:SI2302CDS")
      (libsource (lib "eagle-import") (part "SI2302CDS"))
    )
    (comp (ref "U$23")
      (value "USB-C")
      (footprint "eagle-import:USB-C")
      (libsource (lib "eagle-import") (part "USB-C"))
    )
    (comp (ref "U$24")
      (value "FS8205A-")
      (footprint "eagle-import:FS8205A-")
      (libsource (lib "eagle-import") (part "FS8205A-"))
    )
    (comp (ref "U$25")
      (value "FS8205A-")
      (footprint "eagle-import:FS8205A-")
      (libsource (lib "eagle-import") (part "FS8205A-"))
    )
    (comp (ref "U$26")
      (value "FS8205A-")
      (footprint "eagle-import:FS8205A-")
      (libsource (lib "eagle-import") (part "FS8205A-"))
    )
    (comp (ref "U$31")
      (value "HY2120")
      (footprint "eagle-import:HY2120")
      (libsource (lib "eagle-import") (part "HY2120"))
    )
    (comp (ref "U$32")
      (value "HY2213")
      (footprint "eagle-import:HY2213")
      (libsource (lib "eagle-import") (part "HY2213"))
    )
    (comp (ref "U$33")
      (value "HY2213")
      (footprint "eagle-import:HY2213")
      (libsource (lib "eagle-import") (part "HY2213"))
    )
    (comp (ref "U$34")
      (value "SI2302CDS")
      (footprint "eagle-import:SI2302CDS")
      (libsource (lib "eagle-import") (part "SI2302CDS"))
    )
    (comp (ref "U$35")
      (value "SI2302CDS")
      (footprint "eagle-import:SI2302CDS")
      (libsource (lib "eagle-import") (part "SI2302CDS"))
    )
    (comp (ref "U$38")
      (value "HY2120")
      (footprint "eagle-import:HY2120")
      (libsource (lib "eagle-import") (part "HY2120"))
    )
    (comp (ref "U$39")
      (value "HY2213")
      (footprint "eagle-import:HY2213")
      (libsource (lib "eagle-import") (part "HY2213"))
    )
    (comp (ref "U$40")
      (value "HY2213")
      (footprint "eagle-import:HY2213")
      (libsource (lib "eagle-import") (part "HY2213"))
    )
    (comp (ref "U$41")
      (value "SI2302CDS")
      (footprint "eagle-import:SI2302CDS")
      (libsource (lib "eagle-import") (part "SI2302CDS"))
    )
    (comp (ref "U$42")
      (value "SI2302CDS")
      (footprint "eagle-import:SI2302CDS")
      (libsource (lib "eagle-import") (part "SI2302CDS"))
    )
    (comp (ref "U$45")
      (value "HY2120")
      (footprint "eagle-import:HY2120")
      (libsource (lib "eagle-import") (part "HY2120"))
    )
    (comp (ref "U$46")
      (value "HY2213")
      (footprint "eagle-import:HY2213")
      (libsource (lib "eagle-import") (part "HY2213"))
    )
    (comp (ref "U$47")
      (value "HY2213")
      (footprint "eagle-import:HY2213")
      (libsource (lib "eagle-import") (part "HY2213"))
    )
    (comp (ref "U$48")
      (value "SI2302CDS")
      (footprint "eagle-import:SI2302CDS")
      (libsource (lib "eagle-import") (part "SI2302CDS"))
    )
    (comp (ref "U$49")
      (value "SI2302CDS")
      (footprint "eagle-import:SI2302CDS")
      (libsource (lib "eagle-import") (part "SI2302CDS"))
    )
    (comp (ref "U$57")
      (value "INA219AID")
      (footprint "eagle-import:INA219AID")
      (libsource (lib "eagle-import") (part "INA219AID"))
    )
    (comp (ref "U$59")
      (value "LTC3119")
      (footprint "eagle-import:LTC3119")
      (libsource (lib "eagle-import") (part "LTC3119"))
    )
    (comp (ref "U$60")
      (value "AD5272")
      (footprint "eagle-import:AD5272")
      (libsource (lib "eagle-import") (part "AD5272"))
    )
  )
  (nets
    (net (code "1") (name "/1W") (class "Default")
      (node (ref "AB1") (pin "5") (pinfunction "5_5") (pintype "passive"))
      (node (ref "AB2") (pin "5") (pinfunction "5_5") (pintype "passive"))
      (node (ref "AB3") (pin "5") (pinfunction "5_5") (pintype "passive"))
      (node (ref "IC2") (pin "17") (pinfunction "PA7_17") (pintype "bidirectional"))
    )
    (net (code "2") (name "/5V") (class "Default")
      (node (ref "BSK4") (pin "8") (pinfunction "8_8") (pintype "passive"))
      (node (ref "MICRO") (pin "5V") (pinfunction "1_5V") (pintype "passive"))
    )
    (net (code "3") (name "/90") (class "Default")
      (node (ref "R65") (pin "1") (pinfunction "1_1") (pintype "passive"))
      (node (ref "R66") (pin "2") (pinfunction "2_2") (pintype "passive"))
      (node (ref "R67") (pin "2") (pinfunction "2_2") (pintype "passive"))
      (node (ref "U$59") (pin "15") (pinfunction "MPPC_15") (pintype "bidirectional"))
    )
    (net (code "4") (name "/B-1") (class "Default")
      (node (ref "AB1") (pin "6") (pinfunction "6_6") (pintype "passive"))
      (node (ref "C1") (pin "2") (pinfunction "2_2") (pintype "passive"))
      (node (ref "C2") (pin "2") (pinfunction "2_2") (pintype "passive"))
      (node (ref "C4") (pin "2") (pinfunction "2_2") (pintype "passive"))
      (node (ref "R8") (pin "2") (pinfunction "2_2") (pintype "passive"))
      (node (ref "R86") (pin "1") (pinfunction "1_1") (pintype "passive"))
      (node (ref "U$3") (pin "6") (pinfunction "VSS_6") (pintype "bidirectional"))
      (node (ref "U$5") (pin "3") (pinfunction "VSS_3") (pintype "bidirectional"))
      (node (ref "U$7") (pin "3") (pinfunction "D_3") (pintype "bidirectional"))
    )
    (net (code "5") (name "/B-2") (class "Default")
      (node (ref "AB1") (pin "1") (pinfunction "1_1") (pintype "passive"))
      (node (ref "C25") (pin "2") (pinfunction "2_2") (pintype "passive"))
      (node (ref "C26") (pin "2") (pinfunction "2_2") (pintype "passive"))
      (node (ref "C28") (pin "2") (pinfunction "2_2") (pintype "passive"))
      (node (ref "R100") (pin "1") (pinfunction "1_1") (pintype "passive"))
      (node (ref "R56") (pin "2") (pinfunction "2_2") (pintype "passive"))
      (node (ref "U$45") (pin "6") (pinfunction "VSS_6") (pintype "bidirectional"))
      (node (ref "U$47") (pin "3") (pinfunction "VSS_3") (pintype "bidirectional"))
      (node (ref "U$49") (pin "3") (pinfunction "D_3") (pintype "bidirectional"))
    )
    (net (code "6") (name "/B-3") (class "Default")
      (node (ref "AB2") (pin "6") (pinfunction "6_6") (pintype "passive"))
      (node (ref "C5") (pin "2") (pinfunction "2_2") (pintype "passive"))
      (node (ref "C6") (pin "2") (pinfunction "2_2") (pintype "passive"))
      (node (ref "C8") (pin "2") (pinfunction "2_2") (pintype "passive"))
      (node (ref "R16") (pin "2") (pinfunction "2_2") (pintype "passive"))
      (node (ref "R84") (pin "1") (pinfunction "1_1") (pintype "passive"))
      (node (ref "U$10") (pin "6") (pinfunction "VSS_6") (pintype "bidirectional"))
      (node (ref "U$12") (pin "3") (pinfunction "VSS_3") (pintype "bidirectional"))
      (node (ref "U$14") (pin "3") (pinfunction "D_3") (pintype "bidirectional"))
    )
    (net (code "7") (name "/B-4") (class "Default")
      (node (ref "AB2") (pin "1") (pinfunction "1_1") (pintype "passive"))
      (node (ref "C21") (pin "2") (pinfunction "2_2") (pintype "passive"))
      (node (ref "C22") (pin "2") (pinfunction "2_2") (pintype "passive"))
      (node (ref "C24") (pin "2") (pinfunction "2_2") (pintype "passive"))
      (node (ref "R48") (pin "2") (pinfunction "2_2") (pintype "passive"))
      (node (ref "R85") (pin "1") (pinfunction "1_1") (pintype "passive"))
      (node (ref "U$38") (pin "6") (pinfunction "VSS_6") (pintype "bidirectional"))
      (node (ref "U$40") (pin "3") (pinfunction "VSS_3") (pintype "bidirectional"))
      (node (ref "U$42") (pin "3") (pinfunction "D_3") (pintype "bidirectional"))
    )
    (net (code "8") (name "/B-5") (class "Default")
      (node (ref "AB3") (pin "6") (pinfunction "6_6") (pintype "passive"))
      (node (ref "C10") (pin "2") (pinfunction "2_2") (pintype "passive"))
      (node (ref "C12") (pin "2") (pinfunction "2_2") (pintype "passive"))
      (node (ref "C9") (pin "2") (pinfunction "2_2") (pintype "passive"))
      (node (ref "R24") (pin "2") (pinfunction "2_2") (pintype "passive"))
      (node (ref "R83") (pin "1") (pinfunction "1_1") (pintype "passive"))
      (node (ref "U$17") (pin "6") (pinfunction "VSS_6") (pintype "bidirectional"))
      (node (ref "U$19") (pin "3") (pinfunction "VSS_3") (pintype "bidirectional"))
      (node (ref "U$21") (pin "3") (pinfunction "D_3") (pintype "bidirectional"))
    )
    (net (code "9") (name "/B-6") (class "Default")
      (node (ref "AB3") (pin "1") (pinfunction "1_1") (pintype "passive"))
      (node (ref "C17") (pin "2") (pinfunction "2_2") (pintype "passive"))
      (node (ref "C18") (pin "2") (pinfunction "2_2") (pintype "passive"))
      (node (ref "C20") (pin "2") (pinfunction "2_2") (pintype "passive"))
      (node (ref "R40") (pin "2") (pinfunction "2_2") (pintype "passive"))
      (node (ref "R80") (pin "1") (pinfunction "1_1") (pintype "passive"))
      (node (ref "U$31") (pin "6") (pinfunction "VSS_6") (pintype "bidirectional"))
      (node (ref "U$33") (pin "3") (pinfunction "VSS_3") (pintype "bidirectional"))
      (node (ref "U$35") (pin "3") (pinfunction "D_3") (pintype "bidirectional"))
    )
    (net (code "10") (name "/BMS+") (class "Default")
      (node (ref "AB1") (pin "8") (pinfunction "8_8") (pintype "passive"))
      (node (ref "AB2") (pin "8") (pinfunction "8_8") (pintype "passive"))
      (node (ref "AB3") (pin "8") (pinfunction "8_8") (pintype "passive"))
      (node (ref "LED3") (pin "C") (pinfunction "C_C") (pintype "passive"))
      (node (ref "LED4") (pin "C") (pinfunction "C_C") (pintype "passive"))
      (node (ref "LED5") (pin "C") (pinfunction "C_C") (pintype "passive"))
      (node (ref "LED6") (pin "C") (pinfunction "C_C") (pintype "passive"))
      (node (ref "LED7") (pin "C") (pinfunction "C_C") (pintype "passive"))
      (node (ref "LED8") (pin "C") (pinfunction "C_C") (pintype "passive"))
      (node (ref "R10") (pin "2") (pinfunction "2_2") (pintype "passive"))
      (node (ref "R12") (pin "2") (pinfunction "2_2") (pintype "passive"))
      (node (ref "R14") (pin "2") (pinfunction "2_2") (pintype "passive"))
      (node (ref "R18") (pin "2") (pinfunction "2_2") (pintype "passive"))
      (node (ref "R2") (pin "2") (pinfunction "2_2") (pintype "passive"))
      (node (ref "R20") (pin "2") (pinfunction "2_2") (pintype "passive"))
      (node (ref "R22") (pin "2") (pinfunction "2_2") (pintype "passive"))
      (node (ref "R34") (pin "2") (pinfunction "2_2") (pintype "passive"))
      (node (ref "R36") (pin "2") (pinfunction "2_2") (pintype "passive"))
      (node (ref "R38") (pin "2") (pinfunction "2_2") (pintype "passive"))
      (node (ref "R4") (pin "2") (pinfunction "2_2") (pintype "passive"))
      (node (ref "R42") (pin "2") (pinfunction "2_2") (pintype "passive"))
      (node (ref "R44") (pin "2") (pinfunction "2_2") (pintype "passive"))
      (node (ref "R46") (pin "2") (pinfunction "2_2") (pintype "passive"))
      (node (ref "R50") (pin "2") (pinfunction "2_2") (pintype "passive"))
      (node (ref "R52") (pin "2") (pinfunction "2_2") (pintype "passive"))
      (node (ref "R54") (pin "2") (pinfunction "2_2") (pintype "passive"))
      (node (ref "R6") (pin "2") (pinfunction "2_2") (pintype "passive"))
      (node (ref "R75") (pin "2") (pinfunction "2_2") (pintype "passive"))
      (node (ref "R76") (pin "1") (pinfunction "1_1") (pintype "passive"))
    )
    (net (code "11") (name "/BMS1") (class "Default")
      (node (ref "IC2") (pin "15") (pinfunction "PA5_15") (pintype "bidirectional"))
      (node (ref "R94") (pin "1") (pinfunction "1_1") (pintype "passive"))
      (node (ref "R95") (pin "1") (pinfunction "1_1") (pintype "passive"))
    )
    (net (code "12") (name "/BMS2") (class "Default")
      (node (ref "IC2") (pin "16") (pinfunction "PA6_16") (pintype "bidirectional"))
      (node (ref "R98") (pin "1") (pinfunction "1_1") (pintype "passive"))
      (node (ref "R99") (pin "1") (pinfunction "1_1") (pintype "passive"))
    )
    (net (code "13") (name "/BMS3") (class "Default")
      (node (ref "IC2") (pin "13") (pinfunction "PA3_13") (pintype "bidirectional"))
      (node (ref "R92") (pin "1") (pinfunction "1_1") (pintype "passive"))
      (node (ref "R93") (pin "1") (pinfunction "1_1") (pintype "passive"))
    )
    (net (code "14") (name "/BMS4") (class "Default")
      (node (ref "IC2") (pin "14") (pinfunction "PA4_14") (pintype "bidirectional"))
      (node (ref "R96") (pin "1") (pinfunction "1_1") (pintype "passive"))
      (node (ref "R97") (pin "1") (pinfunction "1_1") (pintype "passive"))
    )
    (net (code "15") (name "/BMS5") (class "Default")
      (node (ref "IC2") (pin "11") (pinfunction "PA1_11") (pintype "bidirectional"))
      (node (ref "R90") (pin "1") (pinfunction "1_1") (pintype "passive"))
      (node (ref "R91") (pin "1") (pinfunction "1_1") (pintype "passive"))
    )
    (net (code "16") (name "/BMS6") (class "Default")
      (node (ref "IC2") (pin "12") (pinfunction "PA2_12") (pintype "bidirectional"))
      (node (ref "R88") (pin "1") (pinfunction "1_1") (pintype "passive"))
      (node (ref "R89") (pin "1") (pinfunction "1_1") (pintype "passive"))
    )
    (net (code "17") (name "/BUS+") (class "Default")
      (node (ref "R71") (pin "2") (pinfunction "2_2") (pintype "passive"))
      (node (ref "R73") (pin "1") (pinfunction "1_1") (pintype "passive"))
      (node (ref "S1") (pin "2") (pinfunction "P_2") (pintype "passive"))
    )
    (net (code "18") (name "/BUSPLUS") (class "Default")
      (node (ref "BSK4") (pin "7") (pinfunction "7_7") (pintype "passive"))
      (node (ref "S1") (pin "1") (pinfunction "O_1") (pintype "passive"))
    )
    (net (code "19") (name "/DPC_RST") (class "Default")
      (node (ref "IC2") (pin "27") (pinfunction "PB14_27") (pintype "bidirectional"))
      (node (ref "U$60") (pin "7") (pinfunction "RESET_7") (pintype "bidirectional"))
    )
    (net (code "20") (name "/DPD_RST") (class "Default")
      (node (ref "AD5272#2") (pin "7") (pinfunction "RESET_7") (pintype "bidirectional"))
      (node (ref "IC2") (pin "28") (pinfunction "PB15_28") (pintype "bidirectional"))
    )
    (net (code "21") (name "/GND") (class "Default")
      (node (ref "AB1") (pin "4") (pinfunction "4_4") (pintype "passive"))
      (node (ref "AB2") (pin "4") (pinfunction "4_4") (pintype "passive"))
      (node (ref "AB3") (pin "4") (pinfunction "4_4") (pintype "passive"))
      (node (ref "AD5272#2") (pin "10") (pinfunction "ADDR_10") (pintype "bidirectional"))
      (node (ref "AD5272#2") (pin "6") (pinfunction "GND_6") (pintype "bidirectional"))
      (node (ref "BSK4") (pin "1") (pinfunction "1_1") (pintype "passive"))
      (node (ref "C15") (pin "2") (pinfunction "2_2") (pintype "passive"))
      (node (ref "C16") (pin "2") (pinfunction "2_2") (pintype "passive"))
      (node (ref "C30") (pin "2") (pinfunction "2_2") (pintype "passive"))
      (node (ref "C31") (pin "2") (pinfunction "2_2") (pintype "passive"))
      (node (ref "C32") (pin "2") (pinfunction "2_2") (pintype "passive"))
      (node (ref "C35") (pin "P$2") (pinfunction "2_P$2") (pintype "passive"))
      (node (ref "C36") (pin "2") (pinfunction "2_2") (pintype "passive"))
      (node (ref "C37") (pin "P$2") (pinfunction "2_P$2") (pintype "passive"))
      (node (ref "C38") (pin "2") (pinfunction "2_2") (pintype "passive"))
      (node (ref "C39") (pin "2") (pinfunction "2_2") (pintype "passive"))
      (node (ref "C42") (pin "2") (pinfunction "2_2") (pintype "passive"))
      (node (ref "C43") (pin "2") (pinfunction "2_2") (pintype "passive"))
      (node (ref "C44") (pin "2") (pinfunction "2_2") (pintype "passive"))
      (node (ref "C45") (pin "2") (pinfunction "2_2") (pintype "passive"))
      (node (ref "C46") (pin "2") (pinfunction "2_2") (pintype "passive"))
      (node (ref "C47") (pin "2") (pinfunction "2_2") (pintype "passive"))
      (node (ref "C48") (pin "2") (pinfunction "2_2") (pintype "passive"))
      (node (ref "C49") (pin "P$2") (pinfunction "2_P$2") (pintype "passive"))
      (node (ref "C50") (pin "P$2") (pinfunction "2_P$2") (pintype "passive"))
      (node (ref "C51") (pin "2") (pinfunction "2_2") (pintype "passive"))
      (node (ref "C52") (pin "2") (pinfunction "2_2") (pintype "passive"))
      (node (ref "C53") (pin "2") (pinfunction "2_2") (pintype "passive"))
      (node (ref "C54") (pin "2") (pinfunction "2_2") (pintype "passive"))
      (node (ref "C55") (pin "2") (pinfunction "2_2") (pintype "passive"))
      (node (ref "IC2") (pin "20") (pinfunction "PB2_20") (pintype "bidirectional"))
      (node (ref "IC2") (pin "23") (pinfunction "VSSA_23") (pintype "power_in"))
      (node (ref "IC2") (pin "35") (pinfunction "VSSA_35") (pintype "power_in"))
      (node (ref "IC2") (pin "44") (pinfunction "BOOT0_44") (pintype "input"))
      (node (ref "IC2") (pin "47") (pinfunction "VSSA_47") (pintype "power_in"))
      (node (ref "IC2") (pin "8") (pinfunction "VSSA_8") (pintype "power_in"))
      (node (ref "INA219#1") (pin "1") (pinfunction "A1_1") (pintype "bidirectional"))
      (node (ref "INA219#1") (pin "2") (pinfunction "A0_2") (pintype "bidirectional"))
      (node (ref "INA219#1") (pin "6") (pinfunction "GND_6") (pintype "bidirectional"))
      (node (ref "MICRO") (pin "GND") (pinfunction "5_GND") (pintype "passive"))
      (node (ref "MICRO") (pin "Z1") (pinfunction "5_Z1") (pintype "passive"))
      (node (ref "MICRO") (pin "Z2") (pinfunction "5_Z2") (pintype "passive"))
      (node (ref "MICRO") (pin "Z3") (pinfunction "5_Z3") (pintype "passive"))
      (node (ref "MICRO") (pin "Z4") (pinfunction "5_Z4") (pintype "passive"))
      (node (ref "R28") (pin "1") (pinfunction "1_1") (pintype "passive"))
      (node (ref "R30") (pin "2") (pinfunction "2_2") (pintype "passive"))
      (node (ref "R62") (pin "1") (pinfunction "1_1") (pintype "passive"))
      (node (ref "R67") (pin "1") (pinfunction "1_1") (pintype "passive"))
      (node (ref "R68") (pin "1") (pinfunction "1_1") (pintype "passive"))
      (node (ref "R70") (pin "1") (pinfunction "1_1") (pintype "passive"))
      (node (ref "R82") (pin "1") (pinfunction "1_1") (pintype "passive"))
      (node (ref "U$1") (pin "23") (pinfunction "S1_23") (pintype "bidirectional"))
      (node (ref "U$15") (pin "23") (pinfunction "S1_23") (pintype "bidirectional"))
      (node (ref "U$16") (pin "14") (pinfunction "SGND_14") (pintype "bidirectional"))
      (node (ref "U$16") (pin "20") (pinfunction "PGND_20") (pintype "bidirectional"))
      (node (ref "U$16") (pin "25") (pinfunction "PGND_25") (pintype "bidirectional"))
      (node (ref "U$16") (pin "28") (pinfunction "PWM_28") (pintype "bidirectional"))
      (node (ref "U$16") (pin "29") (pinfunction "PGND_29") (pintype "bidirectional"))
      (node (ref "U$16") (pin "4") (pinfunction "PGND_4") (pintype "bidirectional"))
      (node (ref "U$16") (pin "9") (pinfunction "PGND_9") (pintype "bidirectional"))
      (node (ref "U$23") (pin "GND0") (pinfunction "GND_GND0") (pintype "bidirectional"))
      (node (ref "U$23") (pin "GND1") (pinfunction "GND_GND1") (pintype "bidirectional"))
      (node (ref "U$24") (pin "23") (pinfunction "S1_23") (pintype "bidirectional"))
      (node (ref "U$25") (pin "23") (pinfunction "S1_23") (pintype "bidirectional"))
      (node (ref "U$26") (pin "23") (pinfunction "S1_23") (pintype "bidirectional"))
      (node (ref "U$57") (pin "1") (pinfunction "A1_1") (pintype "bidirectional"))
      (node (ref "U$57") (pin "6") (pinfunction "GND_6") (pintype "bidirectional"))
      (node (ref "U$59") (pin "14") (pinfunction "SGND_14") (pintype "bidirectional"))
      (node (ref "U$59") (pin "20") (pinfunction "PGND_20") (pintype "bidirectional"))
      (node (ref "U$59") (pin "25") (pinfunction "PGND_25") (pintype "bidirectional"))
      (node (ref "U$59") (pin "28") (pinfunction "PWM_28") (pintype "bidirectional"))
      (node (ref "U$59") (pin "29") (pinfunction "PGND_29") (pintype "bidirectional"))
      (node (ref "U$59") (pin "4") (pinfunction "PGND_4") (pintype "bidirectional"))
      (node (ref "U$59") (pin "9") (pinfunction "PGND_9") (pintype "bidirectional"))
      (node (ref "U$60") (pin "3") (pinfunction "W_3") (pintype "bidirectional"))
      (node (ref "U$60") (pin "4") (pinfunction "VSS_4") (pintype "bidirectional"))
      (node (ref "U$8") (pin "23") (pinfunction "S1_23") (pintype "bidirectional"))
    )
    (net (code "22") (name "/I2CINT") (class "Default")
      (node (ref "BSK4") (pin "3") (pinfunction "3_3") (pintype "passive"))
      (node (ref "IC2") (pin "43") (pinfunction "PB7_43") (pintype "bidirectional"))
    )
    (net (code "23") (name "/INA_BMS+") (class "Default")
      (node (ref "C35") (pin "P$1") (pinfunction "1_P$1") (pintype "passive"))
      (node (ref "C50") (pin "P$1") (pinfunction "1_P$1") (pintype "passive"))
      (node (ref "R63") (pin "2") (pinfunction "2_2") (pintype "passive"))
      (node (ref "R72") (pin "2") (pinfunction "2_2") (pintype "passive"))
      (node (ref "R75") (pin "1") (pinfunction "1_1") (pintype "passive"))
      (node (ref "R77") (pin "1") (pinfunction "1_1") (pintype "passive"))
      (node (ref "U$16") (pin "19") (pinfunction "VIN_19") (pintype "bidirectional"))
      (node (ref "U$16") (pin "22") (pinfunction "PVIN_22") (pintype "bidirectional"))
      (node (ref "U$16") (pin "23") (pinfunction "PVIN_23") (pintype "bidirectional"))
      (node (ref "U$59") (pin "6") (pinfunction "PVOUT_6") (pintype "bidirectional"))
      (node (ref "U$59") (pin "7") (pinfunction "PVOUT_7") (pintype "bidirectional"))
    )
    (net (code "24") (name "/INA_BUS+") (class "Default")
      (node (ref "C37") (pin "P$1") (pinfunction "1_P$1") (pintype "passive"))
      (node (ref "C49") (pin "P$1") (pinfunction "1_P$1") (pintype "passive"))
      (node (ref "R61") (pin "2") (pinfunction "2_2") (pintype "passive"))
      (node (ref "R65") (pin "2") (pinfunction "2_2") (pintype "passive"))
      (node (ref "R71") (pin "1") (pinfunction "1_1") (pintype "passive"))
      (node (ref "R74") (pin "1") (pinfunction "1_1") (pintype "passive"))
      (node (ref "R87") (pin "2") (pinfunction "2_2") (pintype "passive"))
      (node (ref "U$16") (pin "6") (pinfunction "PVOUT_6") (pintype "bidirectional"))
      (node (ref "U$16") (pin "7") (pinfunction "PVOUT_7") (pintype "bidirectional"))
      (node (ref "U$59") (pin "19") (pinfunction "VIN_19") (pintype "bidirectional"))
      (node (ref "U$59") (pin "22") (pinfunction "PVIN_22") (pintype "bidirectional"))
      (node (ref "U$59") (pin "23") (pinfunction "PVIN_23") (pintype "bidirectional"))
    )
    (net (code "25") (name "/N$26") (class "Default")
      (node (ref "R70") (pin "2") (pinfunction "2_2") (pintype "passive"))
      (node (ref "U$60") (pin "6") (pinfunction "GND_6") (pintype "bidirectional"))
    )
    (net (code "26") (name "/N$47") (class "Default")
      (node (ref "AD5272#2") (pin "1") (pinfunction "VDD_1") (pintype "bidirectional"))
      (node (ref "C31") (pin "1") (pinfunction "1_1") (pintype "passive"))
      (node (ref "C51") (pin "1") (pinfunction "1_1") (pintype "passive"))
      (node (ref "C52") (pin "1") (pinfunction "1_1") (pintype "passive"))
      (node (ref "U$16") (pin "11") (pinfunction "SVCC_11") (pintype "bidirectional"))
      (node (ref "U$16") (pin "15") (pinfunction "MPPC_15") (pintype "bidirectional"))
      (node (ref "U$16") (pin "16") (pinfunction "VCC_16") (pintype "bidirectional"))
    )
    (net (code "27") (name "/NRST") (class "Default")
      (node (ref "IC2") (pin "7") (pinfunction "NRST_7") (pintype "bidirectional"))
      (node (ref "R79") (pin "2") (pinfunction "2_2") (pintype "passive"))
      (node (ref "U$23") (pin "NRST/EN") (pinfunction "NRST/EN_NRST/EN") (pintype "bidirectional"))
    )
    (net (code "28") (name "/OC1") (class "Default")
      (node (ref "R95") (pin "2") (pinfunction "2_2") (pintype "passive"))
      (node (ref "U$26") (pin "5") (pinfunction "G2_5") (pintype "bidirectional"))
      (node (ref "U$3") (pin "2") (pinfunction "OC_2") (pintype "bidirectional"))
    )
    (net (code "29") (name "/OC2") (class "Default")
      (node (ref "R99") (pin "2") (pinfunction "2_2") (pintype "passive"))
      (node (ref "U$1") (pin "5") (pinfunction "G2_5") (pintype "bidirectional"))
      (node (ref "U$45") (pin "2") (pinfunction "OC_2") (pintype "bidirectional"))
    )
    (net (code "30") (name "/OC3") (class "Default")
      (node (ref "R93") (pin "2") (pinfunction "2_2") (pintype "passive"))
      (node (ref "U$10") (pin "2") (pinfunction "OC_2") (pintype "bidirectional"))
      (node (ref "U$25") (pin "5") (pinfunction "G2_5") (pintype "bidirectional"))
    )
    (net (code "31") (name "/OC4") (class "Default")
      (node (ref "R97") (pin "2") (pinfunction "2_2") (pintype "passive"))
      (node (ref "U$38") (pin "2") (pinfunction "OC_2") (pintype "bidirectional"))
      (node (ref "U$8") (pin "5") (pinfunction "G2_5") (pintype "bidirectional"))
    )
    (net (code "32") (name "/OC5") (class "Default")
      (node (ref "R91") (pin "2") (pinfunction "2_2") (pintype "passive"))
      (node (ref "U$17") (pin "2") (pinfunction "OC_2") (pintype "bidirectional"))
      (node (ref "U$24") (pin "5") (pinfunction "G2_5") (pintype "bidirectional"))
    )
    (net (code "33") (name "/OC6") (class "Default")
      (node (ref "R89") (pin "2") (pinfunction "2_2") (pintype "passive"))
      (node (ref "U$15") (pin "5") (pinfunction "G2_5") (pintype "bidirectional"))
      (node (ref "U$31") (pin "2") (pinfunction "OC_2") (pintype "bidirectional"))
    )
    (net (code "34") (name "/OD1") (class "Default")
      (node (ref "R94") (pin "2") (pinfunction "2_2") (pintype "passive"))
      (node (ref "U$26") (pin "4") (pinfunction "G1_4") (pintype "bidirectional"))
      (node (ref "U$3") (pin "1") (pinfunction "OD_1") (pintype "bidirectional"))
    )
    (net (code "35") (name "/OD2") (class "Default")
      (node (ref "R98") (pin "2") (pinfunction "2_2") (pintype "passive"))
      (node (ref "U$1") (pin "4") (pinfunction "G1_4") (pintype "bidirectional"))
      (node (ref "U$45") (pin "1") (pinfunction "OD_1") (pintype "bidirectional"))
    )
    (net (code "36") (name "/OD3") (class "Default")
      (node (ref "R92") (pin "2") (pinfunction "2_2") (pintype "passive"))
      (node (ref "U$10") (pin "1") (pinfunction "OD_1") (pintype "bidirectional"))
      (node (ref "U$25") (pin "4") (pinfunction "G1_4") (pintype "bidirectional"))
    )
    (net (code "37") (name "/OD4") (class "Default")
      (node (ref "R96") (pin "2") (pinfunction "2_2") (pintype "passive"))
      (node (ref "U$38") (pin "1") (pinfunction "OD_1") (pintype "bidirectional"))
      (node (ref "U$8") (pin "4") (pinfunction "G1_4") (pintype "bidirectional"))
    )
    (net (code "38") (name "/OD5") (class "Default")
      (node (ref "R90") (pin "2") (pinfunction "2_2") (pintype "passive"))
      (node (ref "U$17") (pin "1") (pinfunction "OD_1") (pintype "bidirectional"))
      (node (ref "U$24") (pin "4") (pinfunction "G1_4") (pintype "bidirectional"))
    )
    (net (code "39") (name "/OD6") (class "Default")
      (node (ref "R88") (pin "2") (pinfunction "2_2") (pintype "passive"))
      (node (ref "U$15") (pin "4") (pinfunction "G1_4") (pintype "bidirectional"))
      (node (ref "U$31") (pin "1") (pinfunction "OD_1") (pintype "bidirectional"))
    )
    (net (code "40") (name "/PGOOD1") (class "Default")
      (node (ref "IC2") (pin "18") (pinfunction "PB0_18") (pintype "bidirectional"))
      (node (ref "U$59") (pin "10") (pinfunction "PGOOD_10") (pintype "bidirectional"))
    )
    (net (code "41") (name "/PGOOD2") (class "Default")
      (node (ref "IC2") (pin "19") (pinfunction "PB1_19") (pintype "bidirectional"))
      (node (ref "U$16") (pin "10") (pinfunction "PGOOD_10") (pintype "bidirectional"))
    )
    (net (code "42") (name "/RX-C") (class "Default")
      (node (ref "IC2") (pin "31") (pinfunction "PA10_31") (pintype "bidirectional"))
      (node (ref "U$23") (pin "RX0") (pinfunction "RX0_RX0") (pintype "bidirectional"))
    )
    (net (code "43") (name "/SCL") (class "Default")
      (node (ref "AD5272#2") (pin "9") (pinfunction "SCL_9") (pintype "bidirectional"))
      (node (ref "IC2") (pin "21") (pinfunction "PB10_21") (pintype "bidirectional"))
      (node (ref "INA219#1") (pin "4") (pinfunction "SCL_4") (pintype "bidirectional"))
      (node (ref "R101") (pin "2") (pinfunction "2_2") (pintype "passive"))
      (node (ref "U$57") (pin "4") (pinfunction "SCL_4") (pintype "bidirectional"))
      (node (ref "U$60") (pin "9") (pinfunction "SCL_9") (pintype "bidirectional"))
    )
    (net (code "44") (name "/SCLTM") (class "Default")
      (node (ref "BSK4") (pin "5") (pinfunction "5_5") (pintype "passive"))
      (node (ref "IC2") (pin "45") (pinfunction "PB8_45") (pintype "bidirectional"))
      (node (ref "R25") (pin "2") (pinfunction "2_2") (pintype "passive"))
    )
    (net (code "45") (name "/SDA") (class "Default")
      (node (ref "AD5272#2") (pin "8") (pinfunction "SDA_8") (pintype "bidirectional"))
      (node (ref "IC2") (pin "22") (pinfunction "PB11_22") (pintype "bidirectional"))
      (node (ref "INA219#1") (pin "3") (pinfunction "SDA_3") (pintype "bidirectional"))
      (node (ref "R102") (pin "2") (pinfunction "2_2") (pintype "passive"))
      (node (ref "U$57") (pin "3") (pinfunction "SDA_3") (pintype "bidirectional"))
      (node (ref "U$60") (pin "8") (pinfunction "SDA_8") (pintype "bidirectional"))
    )
    (net (code "46") (name "/SDATM") (class "Default")
      (node (ref "BSK4") (pin "4") (pinfunction "4_4") (pintype "passive"))
      (node (ref "IC2") (pin "46") (pinfunction "PB9_46") (pintype "bidirectional"))
      (node (ref "R26") (pin "2") (pinfunction "2_2") (pintype "passive"))
    )
    (net (code "47") (name "/SWC") (class "Default")
      (node (ref "IC2") (pin "37") (pinfunction "PA14_37") (pintype "bidirectional"))
      (node (ref "R27") (pin "2") (pinfunction "2_2") (pintype "passive"))
      (node (ref "U$23") (pin "SWC/TXD") (pinfunction "SWC/TXD_SWC/TXD") (pintype "bidirectional"))
    )
    (net (code "48") (name "/SWD") (class "Default")
      (node (ref "IC2") (pin "34") (pinfunction "PA13_34") (pintype "bidirectional"))
      (node (ref "R64") (pin "2") (pinfunction "2_2") (pintype "passive"))
      (node (ref "U$23") (pin "SWD/RXD") (pinfunction "SWD/RXD_SWD/RXD") (pintype "bidirectional"))
    )
    (net (code "49") (name "/TIME") (class "Default")
      (node (ref "BSK4") (pin "2") (pinfunction "2_2") (pintype "passive"))
      (node (ref "IC2") (pin "42") (pinfunction "PB6_42") (pintype "bidirectional"))
    )
    (net (code "50") (name "/TX-C") (class "Default")
      (node (ref "IC2") (pin "30") (pinfunction "PA9_30") (pintype "bidirectional"))
      (node (ref "U$23") (pin "TX0") (pinfunction "TX0_TX0") (pintype "bidirectional"))
    )
    (net (code "51") (name "/VDD") (class "Default")
      (node (ref "AB1") (pin "3") (pinfunction "3_3") (pintype "passive"))
      (node (ref "AB2") (pin "3") (pinfunction "3_3") (pintype "passive"))
      (node (ref "AB3") (pin "3") (pinfunction "3_3") (pintype "passive"))
      (node (ref "BSK4") (pin "6") (pinfunction "6_6") (pintype "passive"))
      (node (ref "C15") (pin "1") (pinfunction "1_1") (pintype "passive"))
      (node (ref "C16") (pin "1") (pinfunction "1_1") (pintype "passive"))
      (node (ref "C48") (pin "1") (pinfunction "1_1") (pintype "passive"))
      (node (ref "C53") (pin "1") (pinfunction "1_1") (pintype "passive"))
      (node (ref "C54") (pin "1") (pinfunction "1_1") (pintype "passive"))
      (node (ref "C55") (pin "1") (pinfunction "1_1") (pintype "passive"))
      (node (ref "IC2") (pin "1") (pinfunction "VBAT_1") (pintype "power_in"))
      (node (ref "IC2") (pin "24") (pinfunction "VDDA_24") (pintype "power_in"))
      (node (ref "IC2") (pin "36") (pinfunction "VDDA_36") (pintype "power_in"))
      (node (ref "IC2") (pin "48") (pinfunction "VDDA_48") (pintype "power_in"))
      (node (ref "IC2") (pin "9") (pinfunction "VDDA_9") (pintype "power_in"))
      (node (ref "INA219#1") (pin "5") (pinfunction "VCC_5") (pintype "bidirectional"))
      (node (ref "PB5") (pin "A") (pinfunction "A_A") (pintype "passive"))
      (node (ref "PWR") (pin "A") (pinfunction "A_A") (pintype "passive"))
      (node (ref "R101") (pin "1") (pinfunction "1_1") (pintype "passive"))
      (node (ref "R102") (pin "1") (pinfunction "1_1") (pintype "passive"))
      (node (ref "R25") (pin "1") (pinfunction "1_1") (pintype "passive"))
      (node (ref "R26") (pin "1") (pinfunction "1_1") (pintype "passive"))
      (node (ref "R27") (pin "1") (pinfunction "1_1") (pintype "passive"))
      (node (ref "R64") (pin "1") (pinfunction "1_1") (pintype "passive"))
      (node (ref "R79") (pin "1") (pinfunction "1_1") (pintype "passive"))
      (node (ref "U$23") (pin "3V3/BUS0") (pinfunction "3V3/BUS_3V3/BUS0") (pintype "bidirectional"))
      (node (ref "U$23") (pin "3V3/BUS1") (pinfunction "3V3/BUS_3V3/BUS1") (pintype "bidirectional"))
      (node (ref "U$57") (pin "2") (pinfunction "A0_2") (pintype "bidirectional"))
      (node (ref "U$57") (pin "5") (pinfunction "VCC_5") (pintype "bidirectional"))
      (node (ref "U$60") (pin "10") (pinfunction "ADDR_10") (pintype "bidirectional"))
    )
    (net (code "52") (name "Net-(3,3µH-Pad1)") (class "Default")
      (node (ref "3,3µH") (pin "1") (pinfunction "1_1") (pintype "bidirectional"))
      (node (ref "C34") (pin "1") (pinfunction "1_1") (pintype "passive"))
      (node (ref "U$59") (pin "5") (pinfunction "SW2_5") (pintype "bidirectional"))
      (node (ref "U$59") (pin "8") (pinfunction "SW2_8") (pintype "bidirectional"))
    )
    (net (code "53") (name "Net-(3,3µH-Pad2)") (class "Default")
      (node (ref "3,3µH") (pin "2") (pinfunction "2_2") (pintype "bidirectional"))
      (node (ref "C33") (pin "1") (pinfunction "1_1") (pintype "passive"))
      (node (ref "U$59") (pin "21") (pinfunction "SW1_21") (pintype "bidirectional"))
      (node (ref "U$59") (pin "24") (pinfunction "SW1_24") (pintype "bidirectional"))
    )
    (net (code "54") (name "Net-(3,3µH1-Pad1)") (class "Default")
      (node (ref "3,3µH1") (pin "1") (pinfunction "1_1") (pintype "bidirectional"))
      (node (ref "C14") (pin "1") (pinfunction "1_1") (pintype "passive"))
      (node (ref "U$16") (pin "5") (pinfunction "SW2_5") (pintype "bidirectional"))
      (node (ref "U$16") (pin "8") (pinfunction "SW2_8") (pintype "bidirectional"))
    )
    (net (code "55") (name "Net-(3,3µH1-Pad2)") (class "Default")
      (node (ref "3,3µH1") (pin "2") (pinfunction "2_2") (pintype "bidirectional"))
      (node (ref "C13") (pin "1") (pinfunction "1_1") (pintype "passive"))
      (node (ref "U$16") (pin "21") (pinfunction "SW1_21") (pintype "bidirectional"))
      (node (ref "U$16") (pin "24") (pinfunction "SW1_24") (pintype "bidirectional"))
    )
    (net (code "56") (name "Net-(AD5272#2-A)") (class "Default")
      (node (ref "AD5272#2") (pin "2") (pinfunction "A_2") (pintype "bidirectional"))
      (node (ref "R61") (pin "1") (pinfunction "1_1") (pintype "passive"))
      (node (ref "U$16") (pin "12") (pinfunction "FB_12") (pintype "bidirectional"))
    )
    (net (code "57") (name "Net-(AD5272#2-CAP)") (class "Default")
      (node (ref "AD5272#2") (pin "5") (pinfunction "CAP_5") (pintype "bidirectional"))
      (node (ref "C29") (pin "1") (pinfunction "1_1") (pintype "passive"))
    )
    (net (code "58") (name "Net-(AD5272#2-VSS)") (class "Default")
      (node (ref "AD5272#2") (pin "3") (pinfunction "W_3") (pintype "bidirectional"))
      (node (ref "AD5272#2") (pin "4") (pinfunction "VSS_4") (pintype "bidirectional"))
      (node (ref "C29") (pin "2") (pinfunction "2_2") (pintype "passive"))
      (node (ref "R30") (pin "1") (pinfunction "1_1") (pintype "passive"))
    )
    (net (code "59") (name "Net-(C005R-1)") (class "Default")
      (node (ref "C005R") (pin "P$1") (pinfunction "1_P$1") (pintype "passive"))
      (node (ref "C46") (pin "1") (pinfunction "1_1") (pintype "passive"))
      (node (ref "IC2") (pin "3") (pinfunction "PC14_3") (pintype "bidirectional"))
    )
    (net (code "60") (name "Net-(C005R-2)") (class "Default")
      (node (ref "C005R") (pin "P$2") (pinfunction "2_P$2") (pintype "passive"))
      (node (ref "C47") (pin "1") (pinfunction "1_1") (pintype "passive"))
      (node (ref "IC2") (pin "4") (pinfunction "PC15_4") (pintype "bidirectional"))
    )
    (net (code "61") (name "Net-(C30-Pad1)") (class "Default")
      (node (ref "C30") (pin "1") (pinfunction "1_1") (pintype "passive"))
      (node (ref "R29") (pin "2") (pinfunction "2_2") (pintype "passive"))
    )
    (net (code "62") (name "Net-(C36-Pad1)") (class "Default")
      (node (ref "C36") (pin "1") (pinfunction "1_1") (pintype "passive"))
      (node (ref "R69") (pin "2") (pinfunction "2_2") (pintype "passive"))
    )
    (net (code "63") (name "Net-(C38-Pad1)") (class "Default")
      (node (ref "C38") (pin "1") (pinfunction "1_1") (pintype "passive"))
      (node (ref "R66") (pin "1") (pinfunction "1_1") (pintype "passive"))
    )
    (net (code "64") (name "Net-(IC2-OSC_IN)") (class "Default")
      (node (ref "C45") (pin "1") (pinfunction "1_1") (pintype "passive"))
      (node (ref "IC2") (pin "5") (pinfunction "OSC_IN_5") (pintype "bidirectional"))
      (node (ref "Q5") (pin "2") (pinfunction "2_2") (pintype "passive"))
      (node (ref "R78") (pin "2") (pinfunction "2_2") (pintype "passive"))
    )
    (net (code "65") (name "Net-(IC2-OSC_OUT)") (class "Default")
      (node (ref "C44") (pin "1") (pinfunction "1_1") (pintype "passive"))
      (node (ref "IC2") (pin "6") (pinfunction "OSC_OUT_6") (pintype "bidirectional"))
      (node (ref "Q5") (pin "1") (pinfunction "1_1") (pintype "passive"))
      (node (ref "R78") (pin "1") (pinfunction "1_1") (pintype "passive"))
    )
    (net (code "66") (name "Net-(IC2-PB5)") (class "Default")
      (node (ref "IC2") (pin "41") (pinfunction "PB5_41") (pintype "bidirectional"))
      (node (ref "R81") (pin "1") (pinfunction "1_1") (pintype "passive"))
    )
    (net (code "67") (name "Net-(INA219#1-IN+)") (class "Default")
      (node (ref "C40") (pin "1") (pinfunction "1_1") (pintype "passive"))
      (node (ref "INA219#1") (pin "8") (pinfunction "IN+_8") (pintype "bidirectional"))
      (node (ref "R73") (pin "2") (pinfunction "2_2") (pintype "passive"))
    )
    (net (code "68") (name "Net-(INA219#1-IN-)") (class "Default")
      (node (ref "C40") (pin "2") (pinfunction "2_2") (pintype "passive"))
      (node (ref "INA219#1") (pin "7") (pinfunction "IN-_7") (pintype "bidirectional"))
      (node (ref "R74") (pin "2") (pinfunction "2_2") (pintype "passive"))
    )
    (net (code "69") (name "Net-(LED3-PadA)") (class "Default")
      (node (ref "LED3") (pin "A") (pinfunction "A_A") (pintype "passive"))
      (node (ref "R80") (pin "2") (pinfunction "2_2") (pintype "passive"))
    )
    (net (code "70") (name "Net-(LED4-PadA)") (class "Default")
      (node (ref "LED4") (pin "A") (pinfunction "A_A") (pintype "passive"))
      (node (ref "R83") (pin "2") (pinfunction "2_2") (pintype "passive"))
    )
    (net (code "71") (name "Net-(LED5-PadA)") (class "Default")
      (node (ref "LED5") (pin "A") (pinfunction "A_A") (pintype "passive"))
      (node (ref "R84") (pin "2") (pinfunction "2_2") (pintype "passive"))
    )
    (net (code "72") (name "Net-(LED6-PadA)") (class "Default")
      (node (ref "LED6") (pin "A") (pinfunction "A_A") (pintype "passive"))
      (node (ref "R85") (pin "2") (pinfunction "2_2") (pintype "passive"))
    )
    (net (code "73") (name "Net-(LED7-PadA)") (class "Default")
      (node (ref "LED7") (pin "A") (pinfunction "A_A") (pintype "passive"))
      (node (ref "R86") (pin "2") (pinfunction "2_2") (pintype "passive"))
    )
    (net (code "74") (name "Net-(LED8-PadA)") (class "Default")
      (node (ref "LED8") (pin "A") (pinfunction "A_A") (pintype "passive"))
      (node (ref "R100") (pin "2") (pinfunction "2_2") (pintype "passive"))
    )
    (net (code "75") (name "Net-(PB5-PadC)") (class "Default")
      (node (ref "PB5") (pin "C") (pinfunction "C_C") (pintype "passive"))
      (node (ref "R81") (pin "2") (pinfunction "2_2") (pintype "passive"))
    )
    (net (code "76") (name "Net-(PWR-PadC)") (class "Default")
      (node (ref "PWR") (pin "C") (pinfunction "C_C") (pintype "passive"))
      (node (ref "R82") (pin "2") (pinfunction "2_2") (pintype "passive"))
    )
    (net (code "77") (name "Net-(U$1-S2)") (class "Default")
      (node (ref "R49") (pin "2") (pinfunction "2_2") (pintype "passive"))
      (node (ref "R56") (pin "1") (pinfunction "1_1") (pintype "passive"))
      (node (ref "U$1") (pin "67") (pinfunction "S2_67") (pintype "bidirectional"))
    )
    (net (code "78") (name "Net-(U$3-CS)") (class "Default")
      (node (ref "R1") (pin "1") (pinfunction "1_1") (pintype "passive"))
      (node (ref "U$3") (pin "3") (pinfunction "CS_3") (pintype "bidirectional"))
    )
    (net (code "79") (name "Net-(U$3-VC)") (class "Default")
      (node (ref "C2") (pin "1") (pinfunction "1_1") (pintype "passive"))
      (node (ref "R3") (pin "1") (pinfunction "1_1") (pintype "passive"))
      (node (ref "U$3") (pin "4") (pinfunction "VC_4") (pintype "bidirectional"))
    )
    (net (code "80") (name "Net-(U$3-VDD)") (class "Default")
      (node (ref "C1") (pin "1") (pinfunction "1_1") (pintype "passive"))
      (node (ref "R2") (pin "1") (pinfunction "1_1") (pintype "passive"))
      (node (ref "U$3") (pin "5") (pinfunction "VDD_5") (pintype "bidirectional"))
    )
    (net (code "81") (name "Net-(U$4-OUT)") (class "Default")
      (node (ref "U$4") (pin "6") (pinfunction "OUT_6") (pintype "bidirectional"))
      (node (ref "U$6") (pin "1") (pinfunction "G_1") (pintype "bidirectional"))
    )
    (net (code "82") (name "Net-(U$4-VDD)") (class "Default")
      (node (ref "C3") (pin "1") (pinfunction "1_1") (pintype "passive"))
      (node (ref "R6") (pin "1") (pinfunction "1_1") (pintype "passive"))
      (node (ref "U$4") (pin "2") (pinfunction "VDD_2") (pintype "bidirectional"))
    )
    (net (code "83") (name "Net-(U$4-VSS)") (class "Default")
      (node (ref "AB1") (pin "7") (pinfunction "7_7") (pintype "passive"))
      (node (ref "C3") (pin "2") (pinfunction "2_2") (pintype "passive"))
      (node (ref "R3") (pin "2") (pinfunction "2_2") (pintype "passive"))
      (node (ref "R5") (pin "2") (pinfunction "2_2") (pintype "passive"))
      (node (ref "R7") (pin "2") (pinfunction "2_2") (pintype "passive"))
      (node (ref "U$4") (pin "3") (pinfunction "VSS_3") (pintype "bidirectional"))
      (node (ref "U$6") (pin "3") (pinfunction "D_3") (pintype "bidirectional"))
    )
    (net (code "84") (name "Net-(U$5-OUT)") (class "Default")
      (node (ref "U$5") (pin "6") (pinfunction "OUT_6") (pintype "bidirectional"))
      (node (ref "U$7") (pin "1") (pinfunction "G_1") (pintype "bidirectional"))
    )
    (net (code "85") (name "Net-(U$5-VDD)") (class "Default")
      (node (ref "C4") (pin "1") (pinfunction "1_1") (pintype "passive"))
      (node (ref "R7") (pin "1") (pinfunction "1_1") (pintype "passive"))
      (node (ref "U$5") (pin "2") (pinfunction "VDD_2") (pintype "bidirectional"))
    )
    (net (code "86") (name "Net-(U$6-S)") (class "Default")
      (node (ref "R4") (pin "1") (pinfunction "1_1") (pintype "passive"))
      (node (ref "U$6") (pin "2") (pinfunction "S_2") (pintype "bidirectional"))
    )
    (net (code "87") (name "Net-(U$7-S)") (class "Default")
      (node (ref "R5") (pin "1") (pinfunction "1_1") (pintype "passive"))
      (node (ref "U$7") (pin "2") (pinfunction "S_2") (pintype "bidirectional"))
    )
    (net (code "88") (name "Net-(U$8-S2)") (class "Default")
      (node (ref "R41") (pin "2") (pinfunction "2_2") (pintype "passive"))
      (node (ref "R48") (pin "1") (pinfunction "1_1") (pintype "passive"))
      (node (ref "U$8") (pin "67") (pinfunction "S2_67") (pintype "bidirectional"))
    )
    (net (code "89") (name "Net-(U$10-CS)") (class "Default")
      (node (ref "R9") (pin "1") (pinfunction "1_1") (pintype "passive"))
      (node (ref "U$10") (pin "3") (pinfunction "CS_3") (pintype "bidirectional"))
    )
    (net (code "90") (name "Net-(U$10-VC)") (class "Default")
      (node (ref "C6") (pin "1") (pinfunction "1_1") (pintype "passive"))
      (node (ref "R11") (pin "1") (pinfunction "1_1") (pintype "passive"))
      (node (ref "U$10") (pin "4") (pinfunction "VC_4") (pintype "bidirectional"))
    )
    (net (code "91") (name "Net-(U$10-VDD)") (class "Default")
      (node (ref "C5") (pin "1") (pinfunction "1_1") (pintype "passive"))
      (node (ref "R10") (pin "1") (pinfunction "1_1") (pintype "passive"))
      (node (ref "U$10") (pin "5") (pinfunction "VDD_5") (pintype "bidirectional"))
    )
    (net (code "92") (name "Net-(U$11-OUT)") (class "Default")
      (node (ref "U$11") (pin "6") (pinfunction "OUT_6") (pintype "bidirectional"))
      (node (ref "U$13") (pin "1") (pinfunction "G_1") (pintype "bidirectional"))
    )
    (net (code "93") (name "Net-(U$11-VDD)") (class "Default")
      (node (ref "C7") (pin "1") (pinfunction "1_1") (pintype "passive"))
      (node (ref "R14") (pin "1") (pinfunction "1_1") (pintype "passive"))
      (node (ref "U$11") (pin "2") (pinfunction "VDD_2") (pintype "bidirectional"))
    )
    (net (code "94") (name "Net-(U$11-VSS)") (class "Default")
      (node (ref "AB2") (pin "7") (pinfunction "7_7") (pintype "passive"))
      (node (ref "C7") (pin "2") (pinfunction "2_2") (pintype "passive"))
      (node (ref "R11") (pin "2") (pinfunction "2_2") (pintype "passive"))
      (node (ref "R13") (pin "2") (pinfunction "2_2") (pintype "passive"))
      (node (ref "R15") (pin "2") (pinfunction "2_2") (pintype "passive"))
      (node (ref "U$11") (pin "3") (pinfunction "VSS_3") (pintype "bidirectional"))
      (node (ref "U$13") (pin "3") (pinfunction "D_3") (pintype "bidirectional"))
    )
    (net (code "95") (name "Net-(U$12-OUT)") (class "Default")
      (node (ref "U$12") (pin "6") (pinfunction "OUT_6") (pintype "bidirectional"))
      (node (ref "U$14") (pin "1") (pinfunction "G_1") (pintype "bidirectional"))
    )
    (net (code "96") (name "Net-(U$12-VDD)") (class "Default")
      (node (ref "C8") (pin "1") (pinfunction "1_1") (pintype "passive"))
      (node (ref "R15") (pin "1") (pinfunction "1_1") (pintype "passive"))
      (node (ref "U$12") (pin "2") (pinfunction "VDD_2") (pintype "bidirectional"))
    )
    (net (code "97") (name "Net-(U$13-S)") (class "Default")
      (node (ref "R12") (pin "1") (pinfunction "1_1") (pintype "passive"))
      (node (ref "U$13") (pin "2") (pinfunction "S_2") (pintype "bidirectional"))
    )
    (net (code "98") (name "Net-(U$14-S)") (class "Default")
      (node (ref "R13") (pin "1") (pinfunction "1_1") (pintype "passive"))
      (node (ref "U$14") (pin "2") (pinfunction "S_2") (pintype "bidirectional"))
    )
    (net (code "99") (name "Net-(U$15-S2)") (class "Default")
      (node (ref "R33") (pin "2") (pinfunction "2_2") (pintype "passive"))
      (node (ref "R40") (pin "1") (pinfunction "1_1") (pintype "passive"))
      (node (ref "U$15") (pin "67") (pinfunction "S2_67") (pintype "bidirectional"))
    )
    (net (code "100") (name "Net-(U$16-BST1)") (class "Default")
      (node (ref "C13") (pin "2") (pinfunction "2_2") (pintype "passive"))
      (node (ref "U$16") (pin "26") (pinfunction "BST1_26") (pintype "bidirectional"))
    )
    (net (code "101") (name "Net-(U$16-BST2)") (class "Default")
      (node (ref "C14") (pin "2") (pinfunction "2_2") (pintype "passive"))
      (node (ref "U$16") (pin "3") (pinfunction "BST2_3") (pintype "bidirectional"))
    )
    (net (code "102") (name "Net-(U$16-RT)") (class "Default")
      (node (ref "R28") (pin "2") (pinfunction "2_2") (pintype "passive"))
      (node (ref "U$16") (pin "17") (pinfunction "RT_17") (pintype "bidirectional"))
    )
    (net (code "103") (name "Net-(U$16-RUN)") (class "Default")
      (node (ref "R63") (pin "1") (pinfunction "1_1") (pintype "passive"))
      (node (ref "U$16") (pin "18") (pinfunction "RUN_18") (pintype "bidirectional"))
    )
    (net (code "104") (name "Net-(U$16-VC)") (class "Default")
      (node (ref "R29") (pin "1") (pinfunction "1_1") (pintype "passive"))
      (node (ref "U$16") (pin "13") (pinfunction "VC_13") (pintype "bidirectional"))
    )
    (net (code "105") (name "Net-(U$17-CS)") (class "Default")
      (node (ref "R17") (pin "1") (pinfunction "1_1") (pintype "passive"))
      (node (ref "U$17") (pin "3") (pinfunction "CS_3") (pintype "bidirectional"))
    )
    (net (code "106") (name "Net-(U$17-VC)") (class "Default")
      (node (ref "C10") (pin "1") (pinfunction "1_1") (pintype "passive"))
      (node (ref "R19") (pin "1") (pinfunction "1_1") (pintype "passive"))
      (node (ref "U$17") (pin "4") (pinfunction "VC_4") (pintype "bidirectional"))
    )
    (net (code "107") (name "Net-(U$17-VDD)") (class "Default")
      (node (ref "C9") (pin "1") (pinfunction "1_1") (pintype "passive"))
      (node (ref "R18") (pin "1") (pinfunction "1_1") (pintype "passive"))
      (node (ref "U$17") (pin "5") (pinfunction "VDD_5") (pintype "bidirectional"))
    )
    (net (code "108") (name "Net-(U$18-OUT)") (class "Default")
      (node (ref "U$18") (pin "6") (pinfunction "OUT_6") (pintype "bidirectional"))
      (node (ref "U$20") (pin "1") (pinfunction "G_1") (pintype "bidirectional"))
    )
    (net (code "109") (name "Net-(U$18-VDD)") (class "Default")
      (node (ref "C11") (pin "1") (pinfunction "1_1") (pintype "passive"))
      (node (ref "R22") (pin "1") (pinfunction "1_1") (pintype "passive"))
      (node (ref "U$18") (pin "2") (pinfunction "VDD_2") (pintype "bidirectional"))
    )
    (net (code "110") (name "Net-(U$18-VSS)") (class "Default")
      (node (ref "AB3") (pin "7") (pinfunction "7_7") (pintype "passive"))
      (node (ref "C11") (pin "2") (pinfunction "2_2") (pintype "passive"))
      (node (ref "R19") (pin "2") (pinfunction "2_2") (pintype "passive"))
      (node (ref "R21") (pin "2") (pinfunction "2_2") (pintype "passive"))
      (node (ref "R23") (pin "2") (pinfunction "2_2") (pintype "passive"))
      (node (ref "U$18") (pin "3") (pinfunction "VSS_3") (pintype "bidirectional"))
      (node (ref "U$20") (pin "3") (pinfunction "D_3") (pintype "bidirectional"))
    )
    (net (code "111") (name "Net-(U$19-OUT)") (class "Default")
      (node (ref "U$19") (pin "6") (pinfunction "OUT_6") (pintype "bidirectional"))
      (node (ref "U$21") (pin "1") (pinfunction "G_1") (pintype "bidirectional"))
    )
    (net (code "112") (name "Net-(U$19-VDD)") (class "Default")
      (node (ref "C12") (pin "1") (pinfunction "1_1") (pintype "passive"))
      (node (ref "R23") (pin "1") (pinfunction "1_1") (pintype "passive"))
      (node (ref "U$19") (pin "2") (pinfunction "VDD_2") (pintype "bidirectional"))
    )
    (net (code "113") (name "Net-(U$20-S)") (class "Default")
      (node (ref "R20") (pin "1") (pinfunction "1_1") (pintype "passive"))
      (node (ref "U$20") (pin "2") (pinfunction "S_2") (pintype "bidirectional"))
    )
    (net (code "114") (name "Net-(U$21-S)") (class "Default")
      (node (ref "R21") (pin "1") (pinfunction "1_1") (pintype "passive"))
      (node (ref "U$21") (pin "2") (pinfunction "S_2") (pintype "bidirectional"))
    )
    (net (code "115") (name "Net-(U$24-S2)") (class "Default")
      (node (ref "R17") (pin "2") (pinfunction "2_2") (pintype "passive"))
      (node (ref "R24") (pin "1") (pinfunction "1_1") (pintype "passive"))
      (node (ref "U$24") (pin "67") (pinfunction "S2_67") (pintype "bidirectional"))
    )
    (net (code "116") (name "Net-(U$25-S2)") (class "Default")
      (node (ref "R16") (pin "1") (pinfunction "1_1") (pintype "passive"))
      (node (ref "R9") (pin "2") (pinfunction "2_2") (pintype "passive"))
      (node (ref "U$25") (pin "67") (pinfunction "S2_67") (pintype "bidirectional"))
    )
    (net (code "117") (name "Net-(U$26-S2)") (class "Default")
      (node (ref "R1") (pin "2") (pinfunction "2_2") (pintype "passive"))
      (node (ref "R8") (pin "1") (pinfunction "1_1") (pintype "passive"))
      (node (ref "U$26") (pin "67") (pinfunction "S2_67") (pintype "bidirectional"))
    )
    (net (code "118") (name "Net-(U$31-CS)") (class "Default")
      (node (ref "R33") (pin "1") (pinfunction "1_1") (pintype "passive"))
      (node (ref "U$31") (pin "3") (pinfunction "CS_3") (pintype "bidirectional"))
    )
    (net (code "119") (name "Net-(U$31-VC)") (class "Default")
      (node (ref "C18") (pin "1") (pinfunction "1_1") (pintype "passive"))
      (node (ref "R35") (pin "1") (pinfunction "1_1") (pintype "passive"))
      (node (ref "U$31") (pin "4") (pinfunction "VC_4") (pintype "bidirectional"))
    )
    (net (code "120") (name "Net-(U$31-VDD)") (class "Default")
      (node (ref "C17") (pin "1") (pinfunction "1_1") (pintype "passive"))
      (node (ref "R34") (pin "1") (pinfunction "1_1") (pintype "passive"))
      (node (ref "U$31") (pin "5") (pinfunction "VDD_5") (pintype "bidirectional"))
    )
    (net (code "121") (name "Net-(U$32-OUT)") (class "Default")
      (node (ref "U$32") (pin "6") (pinfunction "OUT_6") (pintype "bidirectional"))
      (node (ref "U$34") (pin "1") (pinfunction "G_1") (pintype "bidirectional"))
    )
    (net (code "122") (name "Net-(U$32-VDD)") (class "Default")
      (node (ref "C19") (pin "1") (pinfunction "1_1") (pintype "passive"))
      (node (ref "R38") (pin "1") (pinfunction "1_1") (pintype "passive"))
      (node (ref "U$32") (pin "2") (pinfunction "VDD_2") (pintype "bidirectional"))
    )
    (net (code "123") (name "Net-(U$32-VSS)") (class "Default")
      (node (ref "AB3") (pin "2") (pinfunction "2_2") (pintype "passive"))
      (node (ref "C19") (pin "2") (pinfunction "2_2") (pintype "passive"))
      (node (ref "R35") (pin "2") (pinfunction "2_2") (pintype "passive"))
      (node (ref "R37") (pin "2") (pinfunction "2_2") (pintype "passive"))
      (node (ref "R39") (pin "2") (pinfunction "2_2") (pintype "passive"))
      (node (ref "U$32") (pin "3") (pinfunction "VSS_3") (pintype "bidirectional"))
      (node (ref "U$34") (pin "3") (pinfunction "D_3") (pintype "bidirectional"))
    )
    (net (code "124") (name "Net-(U$33-OUT)") (class "Default")
      (node (ref "U$33") (pin "6") (pinfunction "OUT_6") (pintype "bidirectional"))
      (node (ref "U$35") (pin "1") (pinfunction "G_1") (pintype "bidirectional"))
    )
    (net (code "125") (name "Net-(U$33-VDD)") (class "Default")
      (node (ref "C20") (pin "1") (pinfunction "1_1") (pintype "passive"))
      (node (ref "R39") (pin "1") (pinfunction "1_1") (pintype "passive"))
      (node (ref "U$33") (pin "2") (pinfunction "VDD_2") (pintype "bidirectional"))
    )
    (net (code "126") (name "Net-(U$34-S)") (class "Default")
      (node (ref "R36") (pin "1") (pinfunction "1_1") (pintype "passive"))
      (node (ref "U$34") (pin "2") (pinfunction "S_2") (pintype "bidirectional"))
    )
    (net (code "127") (name "Net-(U$35-S)") (class "Default")
      (node (ref "R37") (pin "1") (pinfunction "1_1") (pintype "passive"))
      (node (ref "U$35") (pin "2") (pinfunction "S_2") (pintype "bidirectional"))
    )
    (net (code "128") (name "Net-(U$38-CS)") (class "Default")
      (node (ref "R41") (pin "1") (pinfunction "1_1") (pintype "passive"))
      (node (ref "U$38") (pin "3") (pinfunction "CS_3") (pintype "bidirectional"))
    )
    (net (code "129") (name "Net-(U$38-VC)") (class "Default")
      (node (ref "C22") (pin "1") (pinfunction "1_1") (pintype "passive"))
      (node (ref "R43") (pin "1") (pinfunction "1_1") (pintype "passive"))
      (node (ref "U$38") (pin "4") (pinfunction "VC_4") (pintype "bidirectional"))
    )
    (net (code "130") (name "Net-(U$38-VDD)") (class "Default")
      (node (ref "C21") (pin "1") (pinfunction "1_1") (pintype "passive"))
      (node (ref "R42") (pin "1") (pinfunction "1_1") (pintype "passive"))
      (node (ref "U$38") (pin "5") (pinfunction "VDD_5") (pintype "bidirectional"))
    )
    (net (code "131") (name "Net-(U$39-OUT)") (class "Default")
      (node (ref "U$39") (pin "6") (pinfunction "OUT_6") (pintype "bidirectional"))
      (node (ref "U$41") (pin "1") (pinfunction "G_1") (pintype "bidirectional"))
    )
    (net (code "132") (name "Net-(U$39-VDD)") (class "Default")
      (node (ref "C23") (pin "1") (pinfunction "1_1") (pintype "passive"))
      (node (ref "R46") (pin "1") (pinfunction "1_1") (pintype "passive"))
      (node (ref "U$39") (pin "2") (pinfunction "VDD_2") (pintype "bidirectional"))
    )
    (net (code "133") (name "Net-(U$39-VSS)") (class "Default")
      (node (ref "AB2") (pin "2") (pinfunction "2_2") (pintype "passive"))
      (node (ref "C23") (pin "2") (pinfunction "2_2") (pintype "passive"))
      (node (ref "R43") (pin "2") (pinfunction "2_2") (pintype "passive"))
      (node (ref "R45") (pin "2") (pinfunction "2_2") (pintype "passive"))
      (node (ref "R47") (pin "2") (pinfunction "2_2") (pintype "passive"))
      (node (ref "U$39") (pin "3") (pinfunction "VSS_3") (pintype "bidirectional"))
      (node (ref "U$41") (pin "3") (pinfunction "D_3") (pintype "bidirectional"))
    )
    (net (code "134") (name "Net-(U$40-OUT)") (class "Default")
      (node (ref "U$40") (pin "6") (pinfunction "OUT_6") (pintype "bidirectional"))
      (node (ref "U$42") (pin "1") (pinfunction "G_1") (pintype "bidirectional"))
    )
    (net (code "135") (name "Net-(U$40-VDD)") (class "Default")
      (node (ref "C24") (pin "1") (pinfunction "1_1") (pintype "passive"))
      (node (ref "R47") (pin "1") (pinfunction "1_1") (pintype "passive"))
      (node (ref "U$40") (pin "2") (pinfunction "VDD_2") (pintype "bidirectional"))
    )
    (net (code "136") (name "Net-(U$41-S)") (class "Default")
      (node (ref "R44") (pin "1") (pinfunction "1_1") (pintype "passive"))
      (node (ref "U$41") (pin "2") (pinfunction "S_2") (pintype "bidirectional"))
    )
    (net (code "137") (name "Net-(U$42-S)") (class "Default")
      (node (ref "R45") (pin "1") (pinfunction "1_1") (pintype "passive"))
      (node (ref "U$42") (pin "2") (pinfunction "S_2") (pintype "bidirectional"))
    )
    (net (code "138") (name "Net-(U$45-CS)") (class "Default")
      (node (ref "R49") (pin "1") (pinfunction "1_1") (pintype "passive"))
      (node (ref "U$45") (pin "3") (pinfunction "CS_3") (pintype "bidirectional"))
    )
    (net (code "139") (name "Net-(U$45-VC)") (class "Default")
      (node (ref "C26") (pin "1") (pinfunction "1_1") (pintype "passive"))
      (node (ref "R51") (pin "1") (pinfunction "1_1") (pintype "passive"))
      (node (ref "U$45") (pin "4") (pinfunction "VC_4") (pintype "bidirectional"))
    )
    (net (code "140") (name "Net-(U$45-VDD)") (class "Default")
      (node (ref "C25") (pin "1") (pinfunction "1_1") (pintype "passive"))
      (node (ref "R50") (pin "1") (pinfunction "1_1") (pintype "passive"))
      (node (ref "U$45") (pin "5") (pinfunction "VDD_5") (pintype "bidirectional"))
    )
    (net (code "141") (name "Net-(U$46-OUT)") (class "Default")
      (node (ref "U$46") (pin "6") (pinfunction "OUT_6") (pintype "bidirectional"))
      (node (ref "U$48") (pin "1") (pinfunction "G_1") (pintype "bidirectional"))
    )
    (net (code "142") (name "Net-(U$46-VDD)") (class "Default")
      (node (ref "C27") (pin "1") (pinfunction "1_1") (pintype "passive"))
      (node (ref "R54") (pin "1") (pinfunction "1_1") (pintype "passive"))
      (node (ref "U$46") (pin "2") (pinfunction "VDD_2") (pintype "bidirectional"))
    )
    (net (code "143") (name "Net-(U$46-VSS)") (class "Default")
      (node (ref "AB1") (pin "2") (pinfunction "2_2") (pintype "passive"))
      (node (ref "C27") (pin "2") (pinfunction "2_2") (pintype "passive"))
      (node (ref "R51") (pin "2") (pinfunction "2_2") (pintype "passive"))
      (node (ref "R53") (pin "2") (pinfunction "2_2") (pintype "passive"))
      (node (ref "R55") (pin "2") (pinfunction "2_2") (pintype "passive"))
      (node (ref "U$46") (pin "3") (pinfunction "VSS_3") (pintype "bidirectional"))
      (node (ref "U$48") (pin "3") (pinfunction "D_3") (pintype "bidirectional"))
    )
    (net (code "144") (name "Net-(U$47-OUT)") (class "Default")
      (node (ref "U$47") (pin "6") (pinfunction "OUT_6") (pintype "bidirectional"))
      (node (ref "U$49") (pin "1") (pinfunction "G_1") (pintype "bidirectional"))
    )
    (net (code "145") (name "Net-(U$47-VDD)") (class "Default")
      (node (ref "C28") (pin "1") (pinfunction "1_1") (pintype "passive"))
      (node (ref "R55") (pin "1") (pinfunction "1_1") (pintype "passive"))
      (node (ref "U$47") (pin "2") (pinfunction "VDD_2") (pintype "bidirectional"))
    )
    (net (code "146") (name "Net-(U$48-S)") (class "Default")
      (node (ref "R52") (pin "1") (pinfunction "1_1") (pintype "passive"))
      (node (ref "U$48") (pin "2") (pinfunction "S_2") (pintype "bidirectional"))
    )
    (net (code "147") (name "Net-(U$49-S)") (class "Default")
      (node (ref "R53") (pin "1") (pinfunction "1_1") (pintype "passive"))
      (node (ref "U$49") (pin "2") (pinfunction "S_2") (pintype "bidirectional"))
    )
    (net (code "148") (name "Net-(U$57-IN+)") (class "Default")
      (node (ref "C41") (pin "1") (pinfunction "1_1") (pintype "passive"))
      (node (ref "R76") (pin "2") (pinfunction "2_2") (pintype "passive"))
      (node (ref "U$57") (pin "8") (pinfunction "IN+_8") (pintype "bidirectional"))
    )
    (net (code "149") (name "Net-(U$57-IN-)") (class "Default")
      (node (ref "C41") (pin "2") (pinfunction "2_2") (pintype "passive"))
      (node (ref "R77") (pin "2") (pinfunction "2_2") (pintype "passive"))
      (node (ref "U$57") (pin "7") (pinfunction "IN-_7") (pintype "bidirectional"))
    )
    (net (code "150") (name "Net-(U$59-BST1)") (class "Default")
      (node (ref "C33") (pin "2") (pinfunction "2_2") (pintype "passive"))
      (node (ref "U$59") (pin "26") (pinfunction "BST1_26") (pintype "bidirectional"))
    )
    (net (code "151") (name "Net-(U$59-BST2)") (class "Default")
      (node (ref "C34") (pin "2") (pinfunction "2_2") (pintype "passive"))
      (node (ref "U$59") (pin "3") (pinfunction "BST2_3") (pintype "bidirectional"))
    )
    (net (code "152") (name "Net-(U$59-FB)") (class "Default")
      (node (ref "R72") (pin "1") (pinfunction "1_1") (pintype "passive"))
      (node (ref "U$59") (pin "12") (pinfunction "FB_12") (pintype "bidirectional"))
      (node (ref "U$60") (pin "2") (pinfunction "A_2") (pintype "bidirectional"))
    )
    (net (code "153") (name "Net-(U$59-RT)") (class "Default")
      (node (ref "R68") (pin "2") (pinfunction "2_2") (pintype "passive"))
      (node (ref "U$59") (pin "17") (pinfunction "RT_17") (pintype "bidirectional"))
    )
    (net (code "154") (name "Net-(U$59-RUN)") (class "Default")
      (node (ref "R62") (pin "2") (pinfunction "2_2") (pintype "passive"))
      (node (ref "R87") (pin "1") (pinfunction "1_1") (pintype "passive"))
      (node (ref "U$59") (pin "18") (pinfunction "RUN_18") (pintype "bidirectional"))
    )
    (net (code "155") (name "Net-(U$59-SVCC)") (class "Default")
      (node (ref "C32") (pin "1") (pinfunction "1_1") (pintype "passive"))
      (node (ref "C39") (pin "1") (pinfunction "1_1") (pintype "passive"))
      (node (ref "C43") (pin "1") (pinfunction "1_1") (pintype "passive"))
      (node (ref "U$59") (pin "11") (pinfunction "SVCC_11") (pintype "bidirectional"))
      (node (ref "U$59") (pin "16") (pinfunction "VCC_16") (pintype "bidirectional"))
      (node (ref "U$60") (pin "1") (pinfunction "VDD_1") (pintype "bidirectional"))
    )
    (net (code "156") (name "Net-(U$59-VC)") (class "Default")
      (node (ref "R69") (pin "1") (pinfunction "1_1") (pintype "passive"))
      (node (ref "U$59") (pin "13") (pinfunction "VC_13") (pintype "bidirectional"))
    )
    (net (code "157") (name "Net-(U$60-CAP)") (class "Default")
      (node (ref "C42") (pin "1") (pinfunction "1_1") (pintype "passive"))
      (node (ref "U$60") (pin "5") (pinfunction "CAP_5") (pintype "bidirectional"))
    )
    (net (code "158") (name "unconnected-(IC2-PA0-WKUP-Pad10)") (class "Default")
      (node (ref "IC2") (pin "10") (pinfunction "PA0-WKUP_10") (pintype "bidirectional"))
    )
    (net (code "159") (name "unconnected-(IC2-PA8-Pad29)") (class "Default")
      (node (ref "IC2") (pin "29") (pinfunction "PA8_29") (pintype "bidirectional"))
    )
    (net (code "160") (name "unconnected-(IC2-PA11-Pad32)") (class "Default")
      (node (ref "IC2") (pin "32") (pinfunction "PA11_32") (pintype "bidirectional"))
    )
    (net (code "161") (name "unconnected-(IC2-PA12-Pad33)") (class "Default")
      (node (ref "IC2") (pin "33") (pinfunction "PA12_33") (pintype "bidirectional"))
    )
    (net (code "162") (name "unconnected-(IC2-PA15-Pad38)") (class "Default")
      (node (ref "IC2") (pin "38") (pinfunction "PA15_38") (pintype "bidirectional"))
    )
    (net (code "163") (name "unconnected-(IC2-PB3-Pad39)") (class "Default")
      (node (ref "IC2") (pin "39") (pinfunction "PB3_39") (pintype "bidirectional"))
    )
    (net (code "164") (name "unconnected-(IC2-PB4-Pad40)") (class "Default")
      (node (ref "IC2") (pin "40") (pinfunction "PB4_40") (pintype "bidirectional"))
    )
    (net (code "165") (name "unconnected-(IC2-PB12-Pad25)") (class "Default")
      (node (ref "IC2") (pin "25") (pinfunction "PB12_25") (pintype "bidirectional"))
    )
    (net (code "166") (name "unconnected-(IC2-PB13-Pad26)") (class "Default")
      (node (ref "IC2") (pin "26") (pinfunction "PB13_26") (pintype "bidirectional"))
    )
    (net (code "167") (name "unconnected-(IC2-PC13-Pad2)") (class "Default")
      (node (ref "IC2") (pin "2") (pinfunction "PC13_2") (pintype "bidirectional"))
    )
    (net (code "168") (name "unconnected-(MICRO-2-PadD-)") (class "Default")
      (node (ref "MICRO") (pin "D-") (pinfunction "2_D-") (pintype "passive"))
    )
    (net (code "169") (name "unconnected-(MICRO-3-PadD+)") (class "Default")
      (node (ref "MICRO") (pin "D+") (pinfunction "3_D+") (pintype "passive"))
    )
    (net (code "170") (name "unconnected-(MICRO-4-PadSENSE)") (class "Default")
      (node (ref "MICRO") (pin "SENSE") (pinfunction "4_SENSE") (pintype "passive"))
    )
    (net (code "171") (name "unconnected-(S1-S-Pad3)") (class "Default")
      (node (ref "S1") (pin "3") (pinfunction "S_3") (pintype "passive"))
    )
    (net (code "172") (name "unconnected-(U$23-PadNC{slash}3V3)") (class "Default")
      (node (ref "U$23") (pin "NC/3V3") (pinfunction "NC/3V3_NC/3V3") (pintype "bidirectional"))
    )
    (net (code "173") (name "unconnected-(U$23-PadNC{slash}GPIO)") (class "Default")
      (node (ref "U$23") (pin "NC/GPIO") (pinfunction "NC/GPIO_NC/GPIO") (pintype "bidirectional"))
    )
    (net (code "174") (name "unconnected-(U$23-PadNC{slash}M1)") (class "Default")
      (node (ref "U$23") (pin "NC/M1") (pinfunction "NC/M1_NC/M1") (pintype "bidirectional"))
    )
  )
)
